# BatteryBoardV2.net
KiCad netlist of a schematic drawn in EAGLE
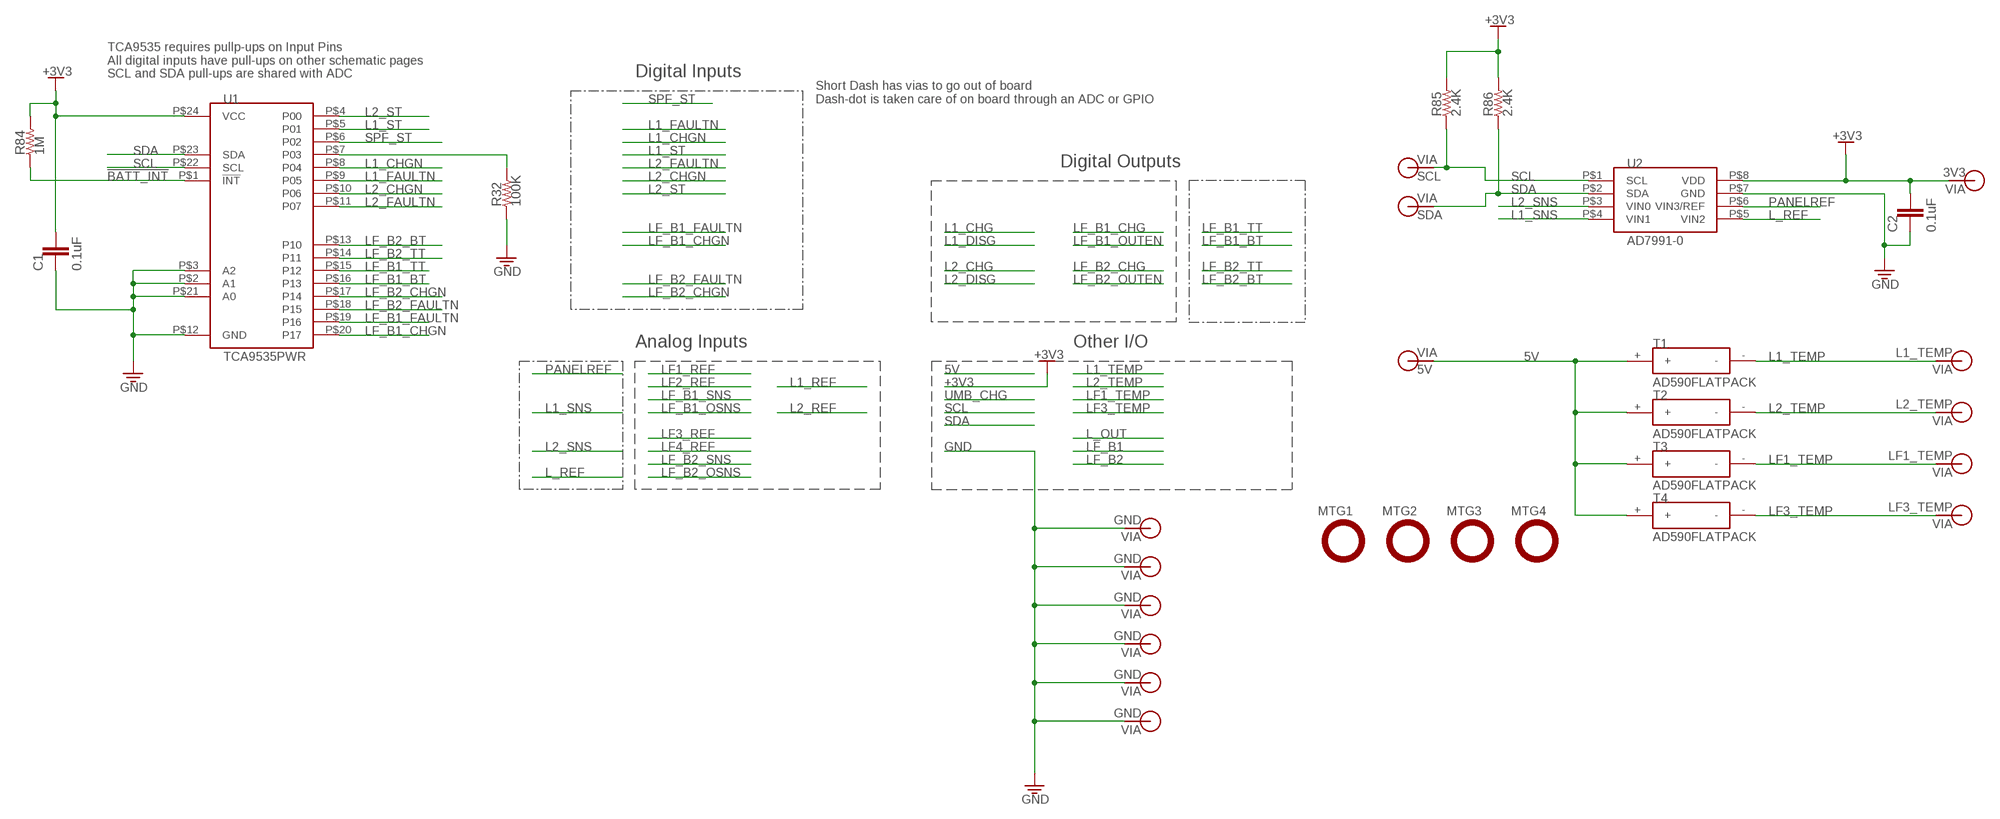
[diagram p0: schematic, sheet 1]
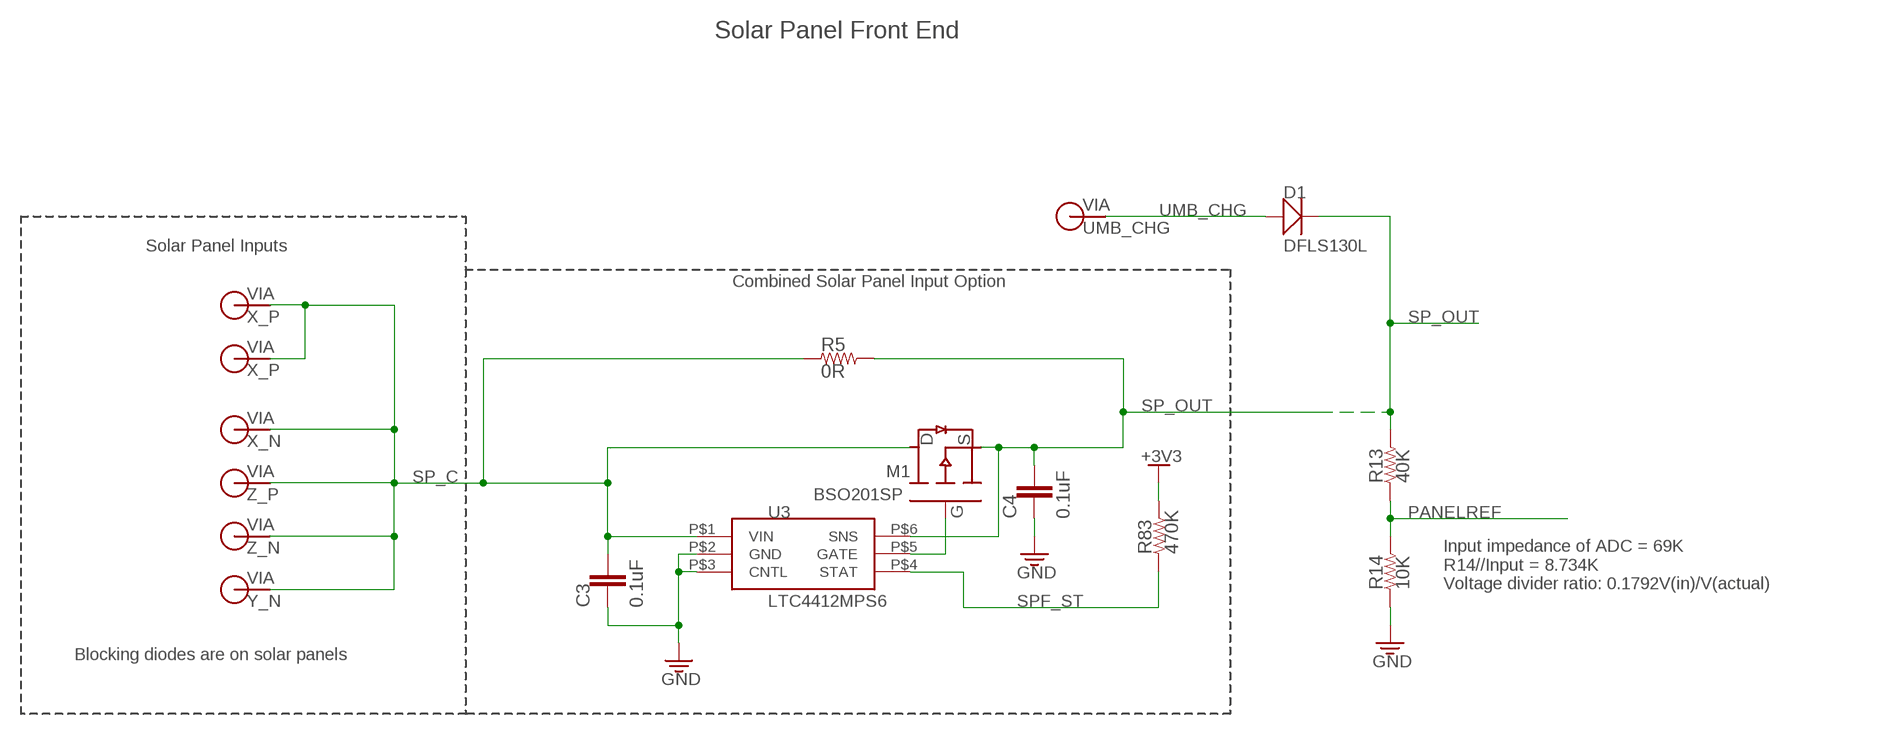
[diagram p1: schematic, sheet 2]
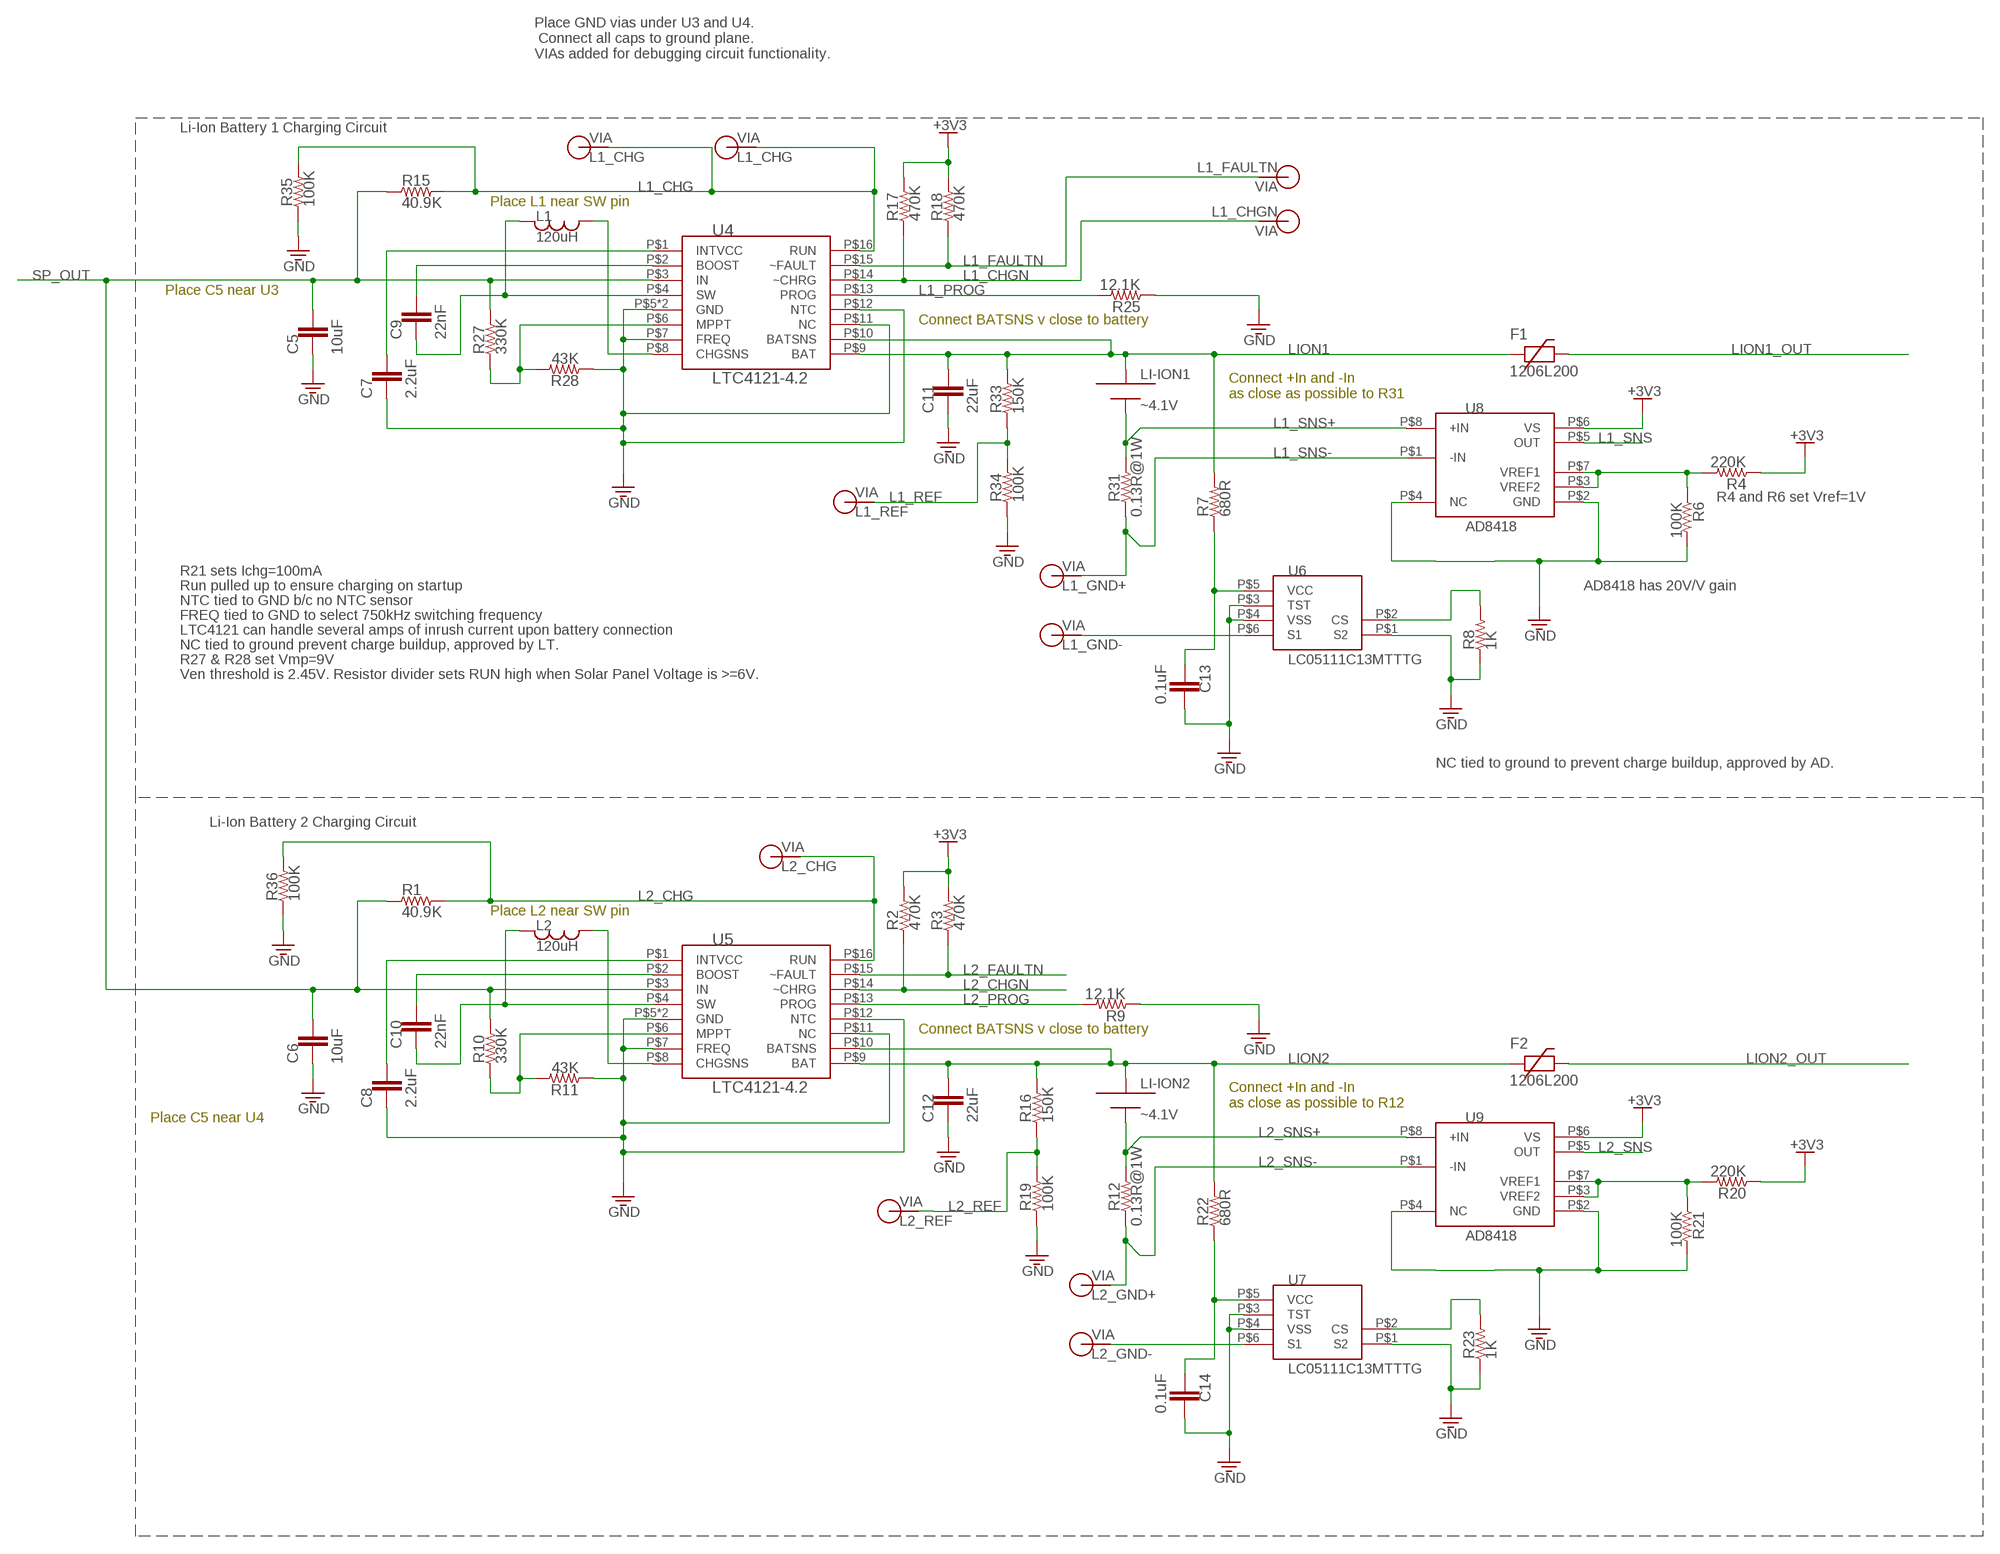
[diagram p2: schematic, sheet 3]
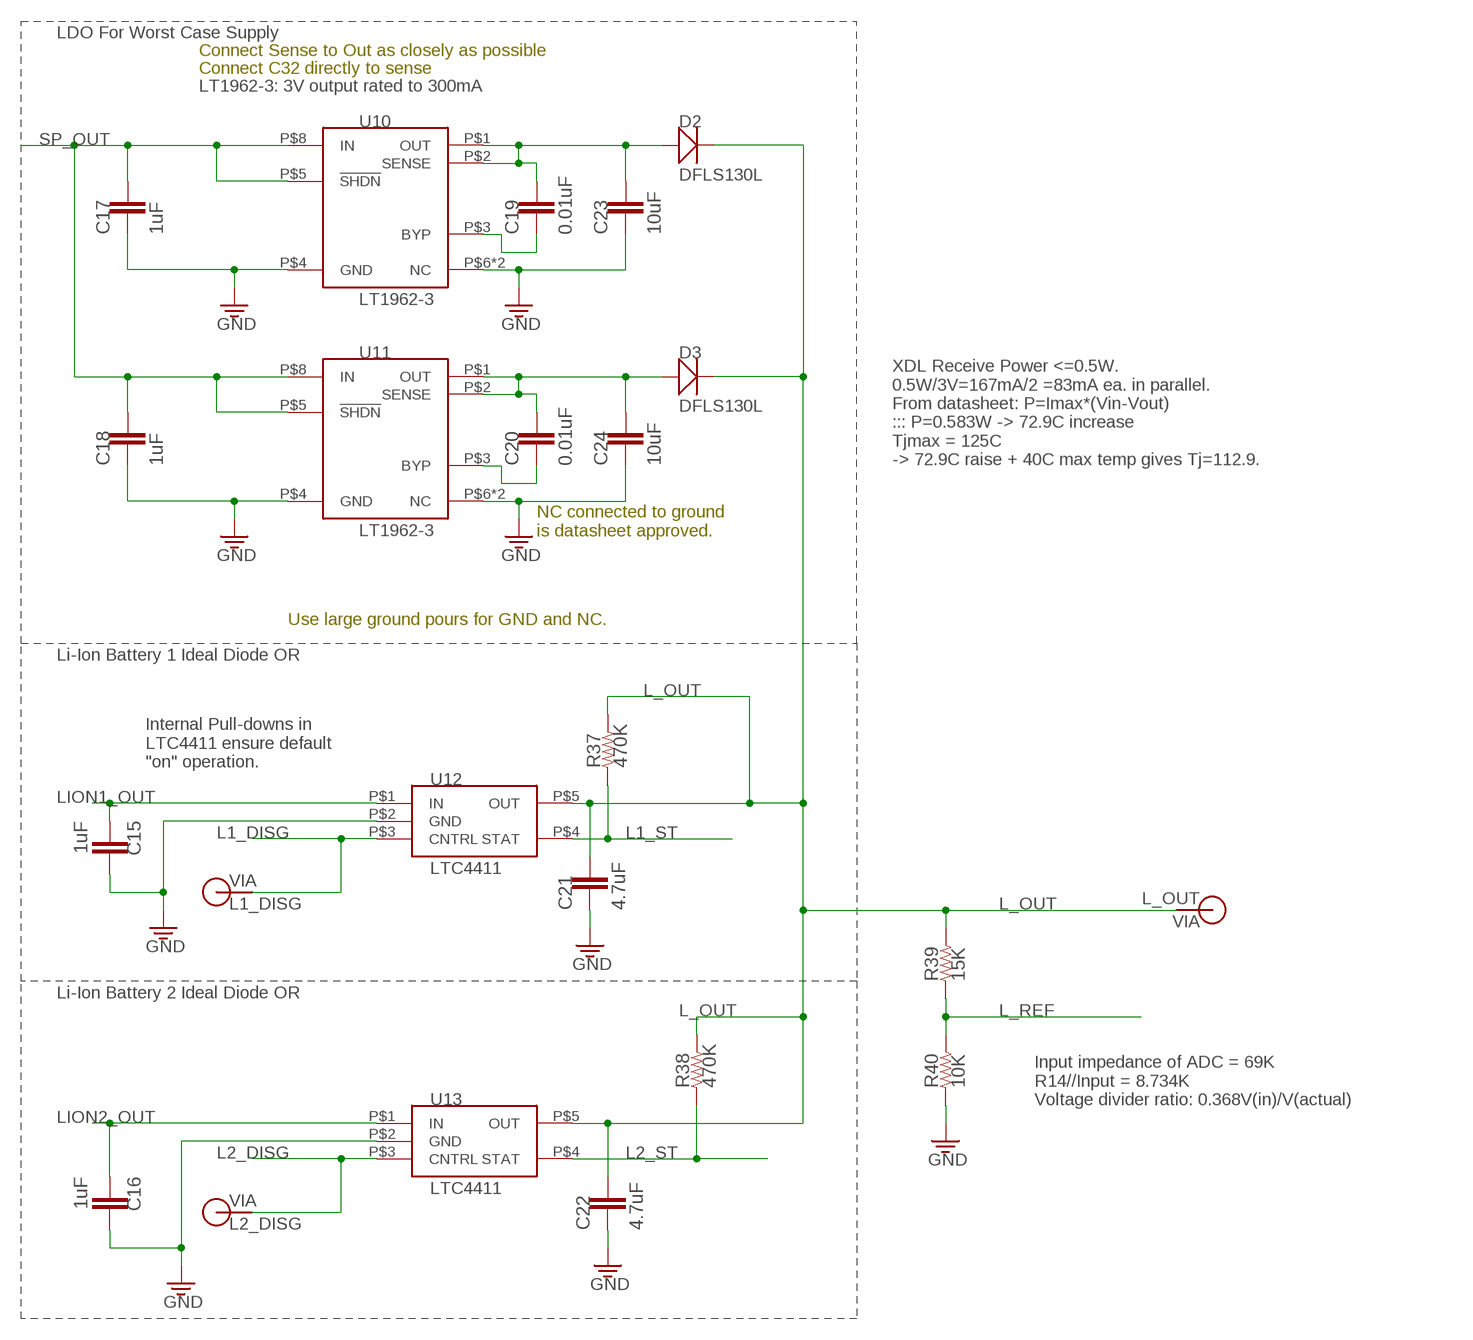
[diagram p3: schematic, sheet 4]
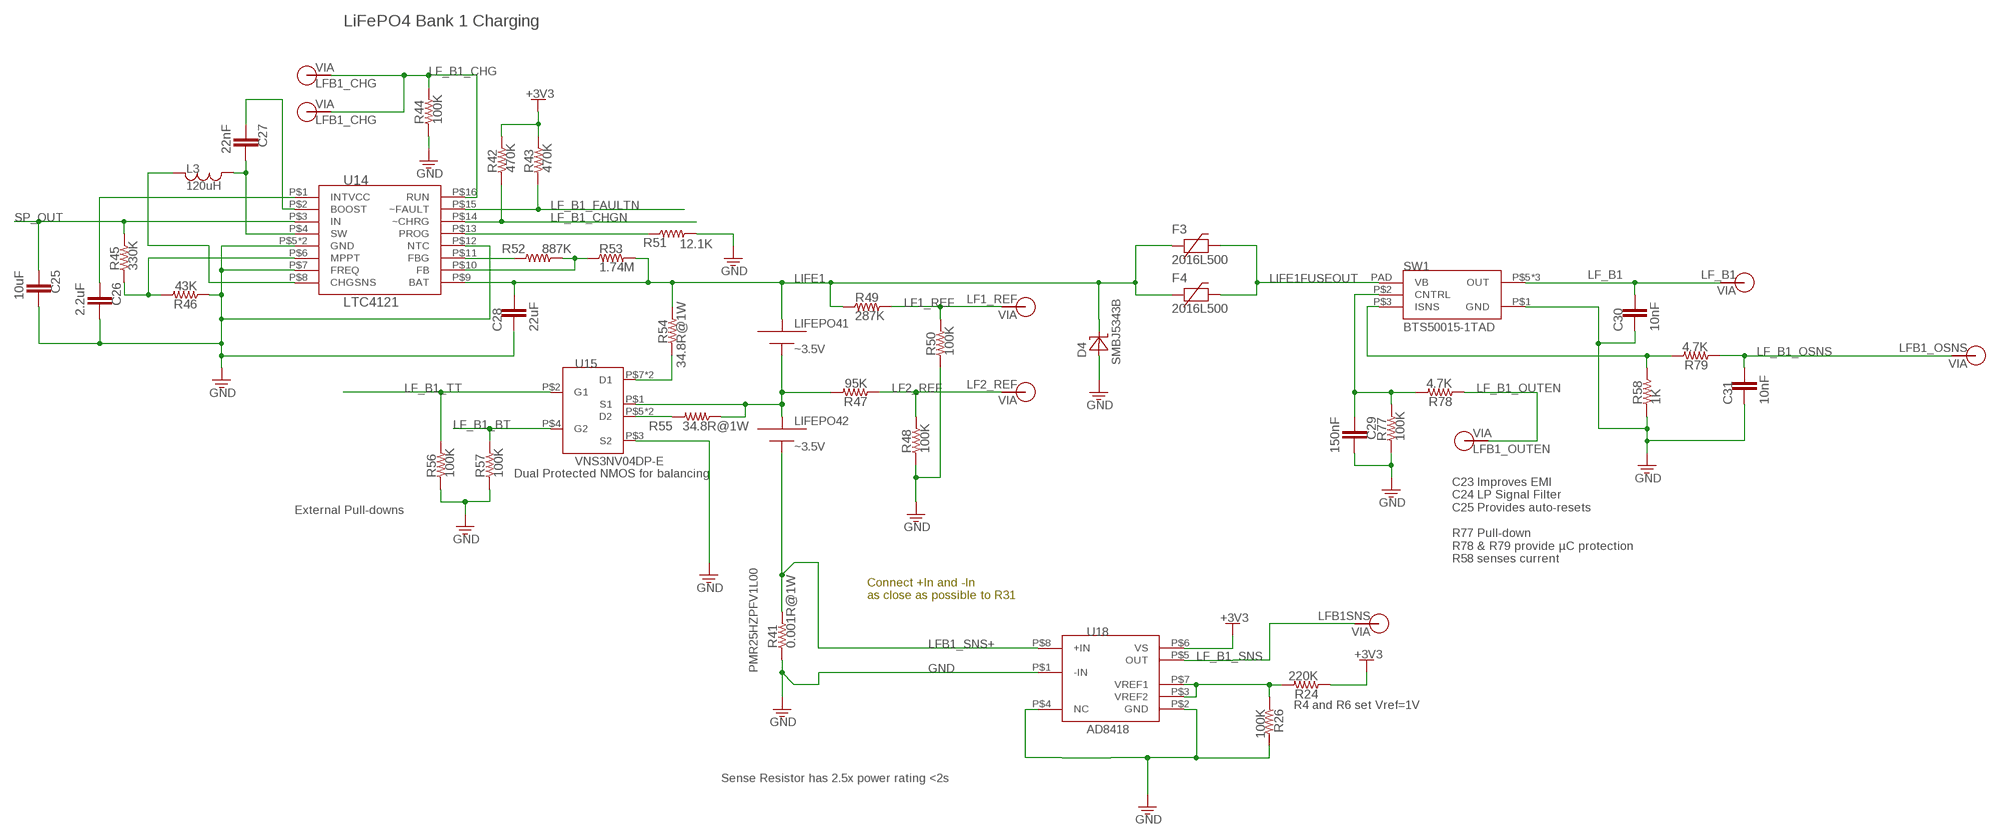
[diagram p4: schematic, sheet 5]
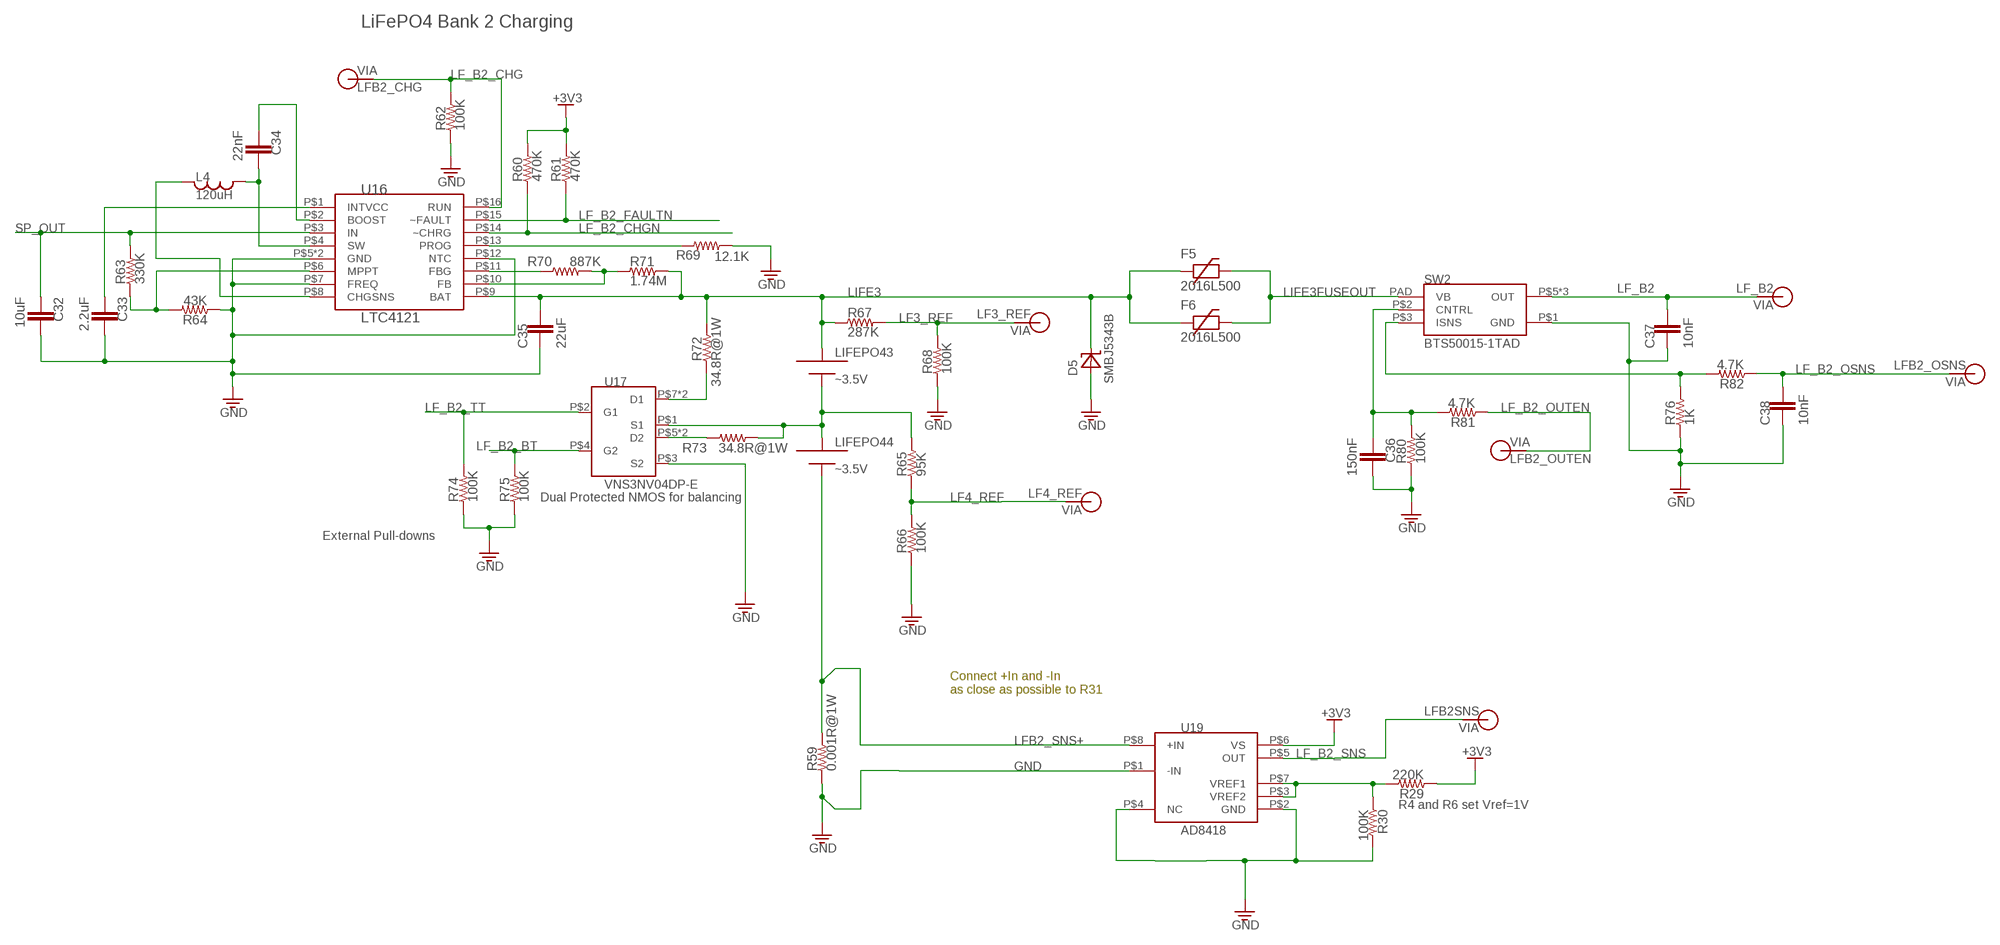
[diagram p5: schematic, sheet 6]

(export (version "E")
  (design (tool "Eeschema 10.0.6"))
  (components
    (comp (ref "C25")
      (value "10uF")
      (footprint "eagle-import:0805")
      (libsource (lib "eagle-import") (part "CAP0805"))
    )
    (comp (ref "C26")
      (value "2.2uF")
      (footprint "eagle-import:0805")
      (libsource (lib "eagle-import") (part "CAP0805"))
    )
    (comp (ref "C27")
      (value "22nF")
      (footprint "eagle-import:0805")
      (libsource (lib "eagle-import") (part "CAP0805"))
    )
    (comp (ref "C28")
      (value "22uF")
      (footprint "eagle-import:0805")
      (libsource (lib "eagle-import") (part "CAP0805"))
    )
    (comp (ref "C29")
      (value "150nF")
      (footprint "eagle-import:0805")
      (libsource (lib "eagle-import") (part "CAP0805"))
    )
    (comp (ref "C30")
      (value "10nF")
      (footprint "eagle-import:0805")
      (libsource (lib "eagle-import") (part "CAP0805"))
    )
    (comp (ref "C31")
      (value "10nF")
      (footprint "eagle-import:0805")
      (libsource (lib "eagle-import") (part "CAP0805"))
    )
    (comp (ref "D4")
      (value "SMBJ5343B")
      (footprint "eagle-import:DO214AA")
      (libsource (lib "eagle-import") (part "SMBJ5343B"))
    )
    (comp (ref "F3")
      (value "2016L500")
      (footprint "eagle-import:2016")
      (libsource (lib "eagle-import") (part "2016L500"))
    )
    (comp (ref "F4")
      (value "2016L500")
      (footprint "eagle-import:2016")
      (libsource (lib "eagle-import") (part "2016L500"))
    )
    (comp (ref "L3")
      (value "120uH")
      (footprint "eagle-import:1812")
      (libsource (lib "eagle-import") (part "IND1812"))
    )
    (comp (ref "LIFEPO41")
      (value "~3.5V")
      (footprint "eagle-import:EQUISAT-BATTERY-VA")
      (libsource (lib "eagle-import") (part "LIFEPO4VA"))
    )
    (comp (ref "LIFEPO42")
      (value "~3.5V")
      (footprint "eagle-import:EQUISAT-BATTERY-VB")
      (libsource (lib "eagle-import") (part "LIFEPO4VB"))
    )
    (comp (ref "R24")
      (value "220K")
      (footprint "eagle-import:0805")
      (libsource (lib "eagle-import") (part "RES0805"))
    )
    (comp (ref "R26")
      (value "100K")
      (footprint "eagle-import:0805")
      (libsource (lib "eagle-import") (part "RES0805"))
    )
    (comp (ref "R41")
      (value "0.001R@1W")
      (footprint "eagle-import:1210")
      (libsource (lib "eagle-import") (part "RES1210"))
    )
    (comp (ref "R42")
      (value "470K")
      (footprint "eagle-import:0805")
      (libsource (lib "eagle-import") (part "RES0805"))
    )
    (comp (ref "R43")
      (value "470K")
      (footprint "eagle-import:0805")
      (libsource (lib "eagle-import") (part "RES0805"))
    )
    (comp (ref "R44")
      (value "100K")
      (footprint "eagle-import:0805")
      (libsource (lib "eagle-import") (part "RES0805"))
    )
    (comp (ref "R45")
      (value "330K")
      (footprint "eagle-import:0805")
      (libsource (lib "eagle-import") (part "RES0805"))
    )
    (comp (ref "R46")
      (value "43K")
      (footprint "eagle-import:0805")
      (libsource (lib "eagle-import") (part "RES0805"))
    )
    (comp (ref "R47")
      (value "95K")
      (footprint "eagle-import:0805")
      (libsource (lib "eagle-import") (part "RES0805"))
    )
    (comp (ref "R48")
      (value "100K")
      (footprint "eagle-import:0805")
      (libsource (lib "eagle-import") (part "RES0805"))
    )
    (comp (ref "R49")
      (value "287K")
      (footprint "eagle-import:0805")
      (libsource (lib "eagle-import") (part "RES0805"))
    )
    (comp (ref "R50")
      (value "100K")
      (footprint "eagle-import:0805")
      (libsource (lib "eagle-import") (part "RES0805"))
    )
    (comp (ref "R51")
      (value "12.1K")
      (footprint "eagle-import:0805")
      (libsource (lib "eagle-import") (part "RES0805"))
    )
    (comp (ref "R52")
      (value "887K")
      (footprint "eagle-import:0805")
      (libsource (lib "eagle-import") (part "RES0805"))
    )
    (comp (ref "R53")
      (value "1.74M")
      (footprint "eagle-import:0805")
      (libsource (lib "eagle-import") (part "RES0805"))
    )
    (comp (ref "R54")
      (value "34.8R@1W")
      (footprint "eagle-import:1210")
      (libsource (lib "eagle-import") (part "RES1210"))
    )
    (comp (ref "R55")
      (value "34.8R@1W")
      (footprint "eagle-import:1210")
      (libsource (lib "eagle-import") (part "RES1210"))
    )
    (comp (ref "R56")
      (value "100K")
      (footprint "eagle-import:0805")
      (libsource (lib "eagle-import") (part "RES0805"))
    )
    (comp (ref "R57")
      (value "100K")
      (footprint "eagle-import:0805")
      (libsource (lib "eagle-import") (part "RES0805"))
    )
    (comp (ref "R58")
      (value "1K")
      (footprint "eagle-import:0805")
      (libsource (lib "eagle-import") (part "RES0805"))
    )
    (comp (ref "R77")
      (value "100K")
      (footprint "eagle-import:0805")
      (libsource (lib "eagle-import") (part "RES0805"))
    )
    (comp (ref "R78")
      (value "4.7K")
      (footprint "eagle-import:0805")
      (libsource (lib "eagle-import") (part "RES0805"))
    )
    (comp (ref "R79")
      (value "4.7K")
      (footprint "eagle-import:0805")
      (libsource (lib "eagle-import") (part "RES0805"))
    )
    (comp (ref "SW1")
      (value "BTS50015-1TAD")
      (footprint "eagle-import:TO-263-7-8")
      (libsource (lib "eagle-import") (part "BTS50015-1TAD"))
    )
    (comp (ref "U14")
      (value "LTC4121")
      (footprint "eagle-import:QFN-16-PAD")
      (libsource (lib "eagle-import") (part "LTC4121"))
    )
    (comp (ref "U15")
      (value "VNS3NV04DP-E")
      (footprint "eagle-import:SO-8")
      (libsource (lib "eagle-import") (part "VNS3NV04DP-E"))
    )
    (comp (ref "U18")
      (value "AD8418")
      (footprint "eagle-import:MSOP-8")
      (libsource (lib "eagle-import") (part "AD8418"))
    )
    (comp (ref "V32")
      (value "LFB1_CHG")
      (footprint "eagle-import:VIA-60MIL-SQ")
      (libsource (lib "eagle-import") (part "VIA60MIL-SQ"))
    )
    (comp (ref "V35")
      (value "LFB1_CHG")
      (footprint "eagle-import:VIA-60MIL")
      (libsource (lib "eagle-import") (part "VIA-60MIL"))
    )
    (comp (ref "V40")
      (value "LFB1SNS")
      (footprint "eagle-import:VIA-60MIL")
      (libsource (lib "eagle-import") (part "VIA-60MIL"))
    )
    (comp (ref "V41")
      (value "LF1_REF")
      (footprint "eagle-import:VIA-60MIL")
      (libsource (lib "eagle-import") (part "VIA-60MIL"))
    )
    (comp (ref "V42")
      (value "LF2_REF")
      (footprint "eagle-import:VIA-60MIL")
      (libsource (lib "eagle-import") (part "VIA-60MIL"))
    )
    (comp (ref "V43")
      (value "LFB1_OUTEN")
      (footprint "eagle-import:VIA-60MIL")
      (libsource (lib "eagle-import") (part "VIA-60MIL"))
    )
    (comp (ref "V45")
      (value "LF_B1")
      (footprint "eagle-import:VIA-120MIL")
      (libsource (lib "eagle-import") (part "VIA-120MIL"))
    )
    (comp (ref "V46")
      (value "LFB1_OSNS")
      (footprint "eagle-import:VIA-60MIL")
      (libsource (lib "eagle-import") (part "VIA-60MIL"))
    )
    (comp (ref "C15")
      (value "1uF")
      (footprint "eagle-import:0805")
      (libsource (lib "eagle-import") (part "CAP0805"))
    )
    (comp (ref "C16")
      (value "1uF")
      (footprint "eagle-import:0805")
      (libsource (lib "eagle-import") (part "CAP0805"))
    )
    (comp (ref "C17")
      (value "1uF")
      (footprint "eagle-import:0805")
      (libsource (lib "eagle-import") (part "CAP0805"))
    )
    (comp (ref "C18")
      (value "1uF")
      (footprint "eagle-import:0805")
      (libsource (lib "eagle-import") (part "CAP0805"))
    )
    (comp (ref "C19")
      (value "0.01uF")
      (footprint "eagle-import:0805")
      (libsource (lib "eagle-import") (part "CAP0805"))
    )
    (comp (ref "C20")
      (value "0.01uF")
      (footprint "eagle-import:0805")
      (libsource (lib "eagle-import") (part "CAP0805"))
    )
    (comp (ref "C21")
      (value "4.7uF")
      (footprint "eagle-import:0805")
      (libsource (lib "eagle-import") (part "CAP0805"))
    )
    (comp (ref "C22")
      (value "4.7uF")
      (footprint "eagle-import:0805")
      (libsource (lib "eagle-import") (part "CAP0805"))
    )
    (comp (ref "C23")
      (value "10uF")
      (footprint "eagle-import:0805")
      (libsource (lib "eagle-import") (part "CAP0805"))
    )
    (comp (ref "C24")
      (value "10uF")
      (footprint "eagle-import:0805")
      (libsource (lib "eagle-import") (part "CAP0805"))
    )
    (comp (ref "D2")
      (value "DFLS130L")
      (footprint "eagle-import:PWRDI-123")
      (libsource (lib "eagle-import") (part "DFLS130L"))
    )
    (comp (ref "D3")
      (value "DFLS130L")
      (footprint "eagle-import:PWRDI-123")
      (libsource (lib "eagle-import") (part "DFLS130L"))
    )
    (comp (ref "R37")
      (value "470K")
      (footprint "eagle-import:0805")
      (libsource (lib "eagle-import") (part "RES0805"))
    )
    (comp (ref "R38")
      (value "470K")
      (footprint "eagle-import:0805")
      (libsource (lib "eagle-import") (part "RES0805"))
    )
    (comp (ref "R39")
      (value "15K")
      (footprint "eagle-import:0805")
      (libsource (lib "eagle-import") (part "RES0805"))
    )
    (comp (ref "R40")
      (value "10K")
      (footprint "eagle-import:0805")
      (libsource (lib "eagle-import") (part "RES0805"))
    )
    (comp (ref "U10")
      (value "LT1962-3")
      (footprint "eagle-import:MSOP-8")
      (libsource (lib "eagle-import") (part "LT1962-3"))
    )
    (comp (ref "U11")
      (value "LT1962-3")
      (footprint "eagle-import:MSOP-8")
      (libsource (lib "eagle-import") (part "LT1962-3"))
    )
    (comp (ref "U12")
      (value "LTC4411")
      (footprint "eagle-import:TSOT23-5")
      (libsource (lib "eagle-import") (part "LTC4411"))
    )
    (comp (ref "U13")
      (value "LTC4411")
      (footprint "eagle-import:TSOT23-5")
      (libsource (lib "eagle-import") (part "LTC4411"))
    )
    (comp (ref "V29")
      (value "L1_DISG")
      (footprint "eagle-import:VIA-60MIL")
      (libsource (lib "eagle-import") (part "VIA-60MIL"))
    )
    (comp (ref "V30")
      (value "L2_DISG")
      (footprint "eagle-import:VIA-60MIL")
      (libsource (lib "eagle-import") (part "VIA-60MIL"))
    )
    (comp (ref "V34")
      (value "L_OUT")
      (footprint "eagle-import:VIA-120MIL")
      (libsource (lib "eagle-import") (part "VIA-120MIL"))
    )
    (comp (ref "C32")
      (value "10uF")
      (footprint "eagle-import:0805")
      (libsource (lib "eagle-import") (part "CAP0805"))
    )
    (comp (ref "C33")
      (value "2.2uF")
      (footprint "eagle-import:0805")
      (libsource (lib "eagle-import") (part "CAP0805"))
    )
    (comp (ref "C34")
      (value "22nF")
      (footprint "eagle-import:0805")
      (libsource (lib "eagle-import") (part "CAP0805"))
    )
    (comp (ref "C35")
      (value "22uF")
      (footprint "eagle-import:0805")
      (libsource (lib "eagle-import") (part "CAP0805"))
    )
    (comp (ref "C36")
      (value "150nF")
      (footprint "eagle-import:0805")
      (libsource (lib "eagle-import") (part "CAP0805"))
    )
    (comp (ref "C37")
      (value "10nF")
      (footprint "eagle-import:0805")
      (libsource (lib "eagle-import") (part "CAP0805"))
    )
    (comp (ref "C38")
      (value "10nF")
      (footprint "eagle-import:0805")
      (libsource (lib "eagle-import") (part "CAP0805"))
    )
    (comp (ref "D5")
      (value "SMBJ5343B")
      (footprint "eagle-import:DO214AA")
      (libsource (lib "eagle-import") (part "SMBJ5343B"))
    )
    (comp (ref "F5")
      (value "2016L500")
      (footprint "eagle-import:2016")
      (libsource (lib "eagle-import") (part "2016L500"))
    )
    (comp (ref "F6")
      (value "2016L500")
      (footprint "eagle-import:2016")
      (libsource (lib "eagle-import") (part "2016L500"))
    )
    (comp (ref "L4")
      (value "120uH")
      (footprint "eagle-import:1812")
      (libsource (lib "eagle-import") (part "IND1812"))
    )
    (comp (ref "LIFEPO43")
      (value "~3.5V")
      (footprint "eagle-import:EQUISAT-BATTERY-VA")
      (libsource (lib "eagle-import") (part "LIFEPO4VA"))
    )
    (comp (ref "LIFEPO44")
      (value "~3.5V")
      (footprint "eagle-import:EQUISAT-BATTERY-VB")
      (libsource (lib "eagle-import") (part "LIFEPO4VB"))
    )
    (comp (ref "R29")
      (value "220K")
      (footprint "eagle-import:0805")
      (libsource (lib "eagle-import") (part "RES0805"))
    )
    (comp (ref "R30")
      (value "100K")
      (footprint "eagle-import:0805")
      (libsource (lib "eagle-import") (part "RES0805"))
    )
    (comp (ref "R59")
      (value "0.001R@1W")
      (footprint "eagle-import:1210")
      (libsource (lib "eagle-import") (part "RES1210"))
    )
    (comp (ref "R60")
      (value "470K")
      (footprint "eagle-import:0805")
      (libsource (lib "eagle-import") (part "RES0805"))
    )
    (comp (ref "R61")
      (value "470K")
      (footprint "eagle-import:0805")
      (libsource (lib "eagle-import") (part "RES0805"))
    )
    (comp (ref "R62")
      (value "100K")
      (footprint "eagle-import:0805")
      (libsource (lib "eagle-import") (part "RES0805"))
    )
    (comp (ref "R63")
      (value "330K")
      (footprint "eagle-import:0805")
      (libsource (lib "eagle-import") (part "RES0805"))
    )
    (comp (ref "R64")
      (value "43K")
      (footprint "eagle-import:0805")
      (libsource (lib "eagle-import") (part "RES0805"))
    )
    (comp (ref "R65")
      (value "95K")
      (footprint "eagle-import:0805")
      (libsource (lib "eagle-import") (part "RES0805"))
    )
    (comp (ref "R66")
      (value "100K")
      (footprint "eagle-import:0805")
      (libsource (lib "eagle-import") (part "RES0805"))
    )
    (comp (ref "R67")
      (value "287K")
      (footprint "eagle-import:0805")
      (libsource (lib "eagle-import") (part "RES0805"))
    )
    (comp (ref "R68")
      (value "100K")
      (footprint "eagle-import:0805")
      (libsource (lib "eagle-import") (part "RES0805"))
    )
    (comp (ref "R69")
      (value "12.1K")
      (footprint "eagle-import:0805")
      (libsource (lib "eagle-import") (part "RES0805"))
    )
    (comp (ref "R70")
      (value "887K")
      (footprint "eagle-import:0805")
      (libsource (lib "eagle-import") (part "RES0805"))
    )
    (comp (ref "R71")
      (value "1.74M")
      (footprint "eagle-import:0805")
      (libsource (lib "eagle-import") (part "RES0805"))
    )
    (comp (ref "R72")
      (value "34.8R@1W")
      (footprint "eagle-import:1210")
      (libsource (lib "eagle-import") (part "RES1210"))
    )
    (comp (ref "R73")
      (value "34.8R@1W")
      (footprint "eagle-import:1210")
      (libsource (lib "eagle-import") (part "RES1210"))
    )
    (comp (ref "R74")
      (value "100K")
      (footprint "eagle-import:0805")
      (libsource (lib "eagle-import") (part "RES0805"))
    )
    (comp (ref "R75")
      (value "100K")
      (footprint "eagle-import:0805")
      (libsource (lib "eagle-import") (part "RES0805"))
    )
    (comp (ref "R76")
      (value "1K")
      (footprint "eagle-import:0805")
      (libsource (lib "eagle-import") (part "RES0805"))
    )
    (comp (ref "R80")
      (value "100K")
      (footprint "eagle-import:0805")
      (libsource (lib "eagle-import") (part "RES0805"))
    )
    (comp (ref "R81")
      (value "4.7K")
      (footprint "eagle-import:0805")
      (libsource (lib "eagle-import") (part "RES0805"))
    )
    (comp (ref "R82")
      (value "4.7K")
      (footprint "eagle-import:0805")
      (libsource (lib "eagle-import") (part "RES0805"))
    )
    (comp (ref "SW2")
      (value "BTS50015-1TAD")
      (footprint "eagle-import:TO-263-7-8")
      (libsource (lib "eagle-import") (part "BTS50015-1TAD"))
    )
    (comp (ref "U16")
      (value "LTC4121")
      (footprint "eagle-import:QFN-16-PAD")
      (libsource (lib "eagle-import") (part "LTC4121"))
    )
    (comp (ref "U17")
      (value "VNS3NV04DP-E")
      (footprint "eagle-import:SO-8")
      (libsource (lib "eagle-import") (part "VNS3NV04DP-E"))
    )
    (comp (ref "U19")
      (value "AD8418")
      (footprint "eagle-import:MSOP-8")
      (libsource (lib "eagle-import") (part "AD8418"))
    )
    (comp (ref "V44")
      (value "LFB2SNS")
      (footprint "eagle-import:VIA-60MIL")
      (libsource (lib "eagle-import") (part "VIA-60MIL"))
    )
    (comp (ref "V47")
      (value "LFB2_CHG")
      (footprint "eagle-import:VIA-60MIL")
      (libsource (lib "eagle-import") (part "VIA-60MIL"))
    )
    (comp (ref "V49")
      (value "LF3_REF")
      (footprint "eagle-import:VIA-60MIL")
      (libsource (lib "eagle-import") (part "VIA-60MIL"))
    )
    (comp (ref "V50")
      (value "LF4_REF")
      (footprint "eagle-import:VIA-60MIL")
      (libsource (lib "eagle-import") (part "VIA-60MIL"))
    )
    (comp (ref "V51")
      (value "LFB2_OUTEN")
      (footprint "eagle-import:VIA-60MIL")
      (libsource (lib "eagle-import") (part "VIA-60MIL"))
    )
    (comp (ref "V53")
      (value "LF_B2")
      (footprint "eagle-import:VIA-120MIL")
      (libsource (lib "eagle-import") (part "VIA-120MIL"))
    )
    (comp (ref "V99")
      (value "LFB2_OSNS")
      (footprint "eagle-import:VIA-60MIL")
      (libsource (lib "eagle-import") (part "VIA-60MIL"))
    )
    (comp (ref "C1")
      (value "0.1uF")
      (footprint "eagle-import:0805")
      (libsource (lib "eagle-import") (part "CAP0805"))
    )
    (comp (ref "C2")
      (value "0.1uF")
      (footprint "eagle-import:0805")
      (libsource (lib "eagle-import") (part "CAP0805"))
    )
    (comp (ref "MTG1")
      (value "MTG-NPTH-#2-CLOSE")
      (footprint "eagle-import:#2-CLOSE-NPTH")
      (libsource (lib "eagle-import") (part "MTG-NPTH-#2-CLOSE"))
    )
    (comp (ref "MTG2")
      (value "MTG-NPTH-#2-CLOSE")
      (footprint "eagle-import:#2-CLOSE-NPTH")
      (libsource (lib "eagle-import") (part "MTG-NPTH-#2-CLOSE"))
    )
    (comp (ref "MTG3")
      (value "MTG-NPTH-#2-CLOSE")
      (footprint "eagle-import:#2-CLOSE-NPTH")
      (libsource (lib "eagle-import") (part "MTG-NPTH-#2-CLOSE"))
    )
    (comp (ref "MTG4")
      (value "MTG-NPTH-#2-CLOSE")
      (footprint "eagle-import:#2-CLOSE-NPTH")
      (libsource (lib "eagle-import") (part "MTG-NPTH-#2-CLOSE"))
    )
    (comp (ref "R32")
      (value "100K")
      (footprint "eagle-import:0805")
      (libsource (lib "eagle-import") (part "RES0805"))
    )
    (comp (ref "R84")
      (value "1M")
      (footprint "eagle-import:0805")
      (libsource (lib "eagle-import") (part "RES0805"))
    )
    (comp (ref "R85")
      (value "2.4K")
      (footprint "eagle-import:0805")
      (libsource (lib "eagle-import") (part "RES0805"))
    )
    (comp (ref "R86")
      (value "2.4K")
      (footprint "eagle-import:0805")
      (libsource (lib "eagle-import") (part "RES0805"))
    )
    (comp (ref "T1")
      (value "AD590FLATPACK")
      (footprint "eagle-import:FLATPACK")
      (libsource (lib "eagle-import") (part "AD590FLATPACK"))
    )
    (comp (ref "T2")
      (value "AD590FLATPACK")
      (footprint "eagle-import:FLATPACK")
      (libsource (lib "eagle-import") (part "AD590FLATPACK"))
    )
    (comp (ref "T3")
      (value "AD590FLATPACK")
      (footprint "eagle-import:FLATPACK")
      (libsource (lib "eagle-import") (part "AD590FLATPACK"))
    )
    (comp (ref "T4")
      (value "AD590FLATPACK")
      (footprint "eagle-import:FLATPACK")
      (libsource (lib "eagle-import") (part "AD590FLATPACK"))
    )
    (comp (ref "U1")
      (value "TCA9535PWR")
      (footprint "eagle-import:TSSOP-24")
      (libsource (lib "eagle-import") (part "TCA9535PWR"))
    )
    (comp (ref "U2")
      (value "AD7991-0")
      (footprint "eagle-import:SOT-23-8")
      (libsource (lib "eagle-import") (part "AD7991-0"))
    )
    (comp (ref "V1")
      (value "GND")
      (footprint "eagle-import:VIA-120MIL")
      (libsource (lib "eagle-import") (part "VIA-120MIL"))
    )
    (comp (ref "V2")
      (value "GND")
      (footprint "eagle-import:VIA-120MIL")
      (libsource (lib "eagle-import") (part "VIA-120MIL"))
    )
    (comp (ref "V3")
      (value "GND")
      (footprint "eagle-import:VIA-60MIL-SQ")
      (libsource (lib "eagle-import") (part "VIA60MIL-SQ"))
    )
    (comp (ref "V4")
      (value "GND")
      (footprint "eagle-import:VIA-120MIL")
      (libsource (lib "eagle-import") (part "VIA-120MIL"))
    )
    (comp (ref "V5")
      (value "SCL")
      (footprint "eagle-import:VIA-60MIL")
      (libsource (lib "eagle-import") (part "VIA-60MIL"))
    )
    (comp (ref "V6")
      (value "SDA")
      (footprint "eagle-import:VIA-60MIL")
      (libsource (lib "eagle-import") (part "VIA-60MIL"))
    )
    (comp (ref "V7")
      (value "5V")
      (footprint "eagle-import:VIA-60MIL")
      (libsource (lib "eagle-import") (part "VIA-60MIL"))
    )
    (comp (ref "V8")
      (value "L1_TEMP")
      (footprint "eagle-import:VIA-60MIL")
      (libsource (lib "eagle-import") (part "VIA-60MIL"))
    )
    (comp (ref "V9")
      (value "L2_TEMP")
      (footprint "eagle-import:VIA-60MIL")
      (libsource (lib "eagle-import") (part "VIA-60MIL"))
    )
    (comp (ref "V10")
      (value "LF1_TEMP")
      (footprint "eagle-import:VIA-60MIL")
      (libsource (lib "eagle-import") (part "VIA-60MIL"))
    )
    (comp (ref "V11")
      (value "LF3_TEMP")
      (footprint "eagle-import:VIA-60MIL")
      (libsource (lib "eagle-import") (part "VIA-60MIL"))
    )
    (comp (ref "V12")
      (value "3V3")
      (footprint "eagle-import:VIA-60MIL")
      (libsource (lib "eagle-import") (part "VIA-60MIL"))
    )
    (comp (ref "V28")
      (value "GND")
      (footprint "eagle-import:VIA-60MIL-SQ")
      (libsource (lib "eagle-import") (part "VIA60MIL-SQ"))
    )
    (comp (ref "V36")
      (value "GND")
      (footprint "eagle-import:VIA-60MIL-SQ")
      (libsource (lib "eagle-import") (part "VIA60MIL-SQ"))
    )
    (comp (ref "C5")
      (value "10uF")
      (footprint "eagle-import:0805")
      (libsource (lib "eagle-import") (part "CAP0805"))
    )
    (comp (ref "C6")
      (value "10uF")
      (footprint "eagle-import:0805")
      (libsource (lib "eagle-import") (part "CAP0805"))
    )
    (comp (ref "C7")
      (value "2.2uF")
      (footprint "eagle-import:0805")
      (libsource (lib "eagle-import") (part "CAP0805"))
    )
    (comp (ref "C8")
      (value "2.2uF")
      (footprint "eagle-import:0805")
      (libsource (lib "eagle-import") (part "CAP0805"))
    )
    (comp (ref "C9")
      (value "22nF")
      (footprint "eagle-import:0805")
      (libsource (lib "eagle-import") (part "CAP0805"))
    )
    (comp (ref "C10")
      (value "22nF")
      (footprint "eagle-import:0805")
      (libsource (lib "eagle-import") (part "CAP0805"))
    )
    (comp (ref "C11")
      (value "22uF")
      (footprint "eagle-import:0805")
      (libsource (lib "eagle-import") (part "CAP0805"))
    )
    (comp (ref "C12")
      (value "22uF")
      (footprint "eagle-import:0805")
      (libsource (lib "eagle-import") (part "CAP0805"))
    )
    (comp (ref "C13")
      (value "0.1uF")
      (footprint "eagle-import:0805")
      (libsource (lib "eagle-import") (part "CAP0805"))
    )
    (comp (ref "C14")
      (value "0.1uF")
      (footprint "eagle-import:0805")
      (libsource (lib "eagle-import") (part "CAP0805"))
    )
    (comp (ref "F1")
      (value "1206L200")
      (footprint "eagle-import:1206")
      (libsource (lib "eagle-import") (part "PTCFUSE1206"))
    )
    (comp (ref "F2")
      (value "1206L200")
      (footprint "eagle-import:1206")
      (libsource (lib "eagle-import") (part "PTCFUSE1206"))
    )
    (comp (ref "L1")
      (value "120uH")
      (footprint "eagle-import:1812")
      (libsource (lib "eagle-import") (part "IND1812"))
    )
    (comp (ref "L2")
      (value "120uH")
      (footprint "eagle-import:1812")
      (libsource (lib "eagle-import") (part "IND1812"))
    )
    (comp (ref "LI-ION1")
      (value "~4.1V")
      (footprint "eagle-import:EQUISAT-BATTERY-VA")
      (libsource (lib "eagle-import") (part "LI-ION"))
    )
    (comp (ref "LI-ION2")
      (value "~4.1V")
      (footprint "eagle-import:EQUISAT-BATTERY-VA")
      (libsource (lib "eagle-import") (part "LI-ION"))
    )
    (comp (ref "R1")
      (value "40.9K")
      (footprint "eagle-import:0805")
      (libsource (lib "eagle-import") (part "RES0805"))
    )
    (comp (ref "R2")
      (value "470K")
      (footprint "eagle-import:0805")
      (libsource (lib "eagle-import") (part "RES0805"))
    )
    (comp (ref "R3")
      (value "470K")
      (footprint "eagle-import:0805")
      (libsource (lib "eagle-import") (part "RES0805"))
    )
    (comp (ref "R4")
      (value "220K")
      (footprint "eagle-import:0805")
      (libsource (lib "eagle-import") (part "RES0805"))
    )
    (comp (ref "R6")
      (value "100K")
      (footprint "eagle-import:0805")
      (libsource (lib "eagle-import") (part "RES0805"))
    )
    (comp (ref "R7")
      (value "680R")
      (footprint "eagle-import:0805")
      (libsource (lib "eagle-import") (part "RES0805"))
    )
    (comp (ref "R8")
      (value "1K")
      (footprint "eagle-import:0805")
      (libsource (lib "eagle-import") (part "RES0805"))
    )
    (comp (ref "R9")
      (value "12.1K")
      (footprint "eagle-import:0805")
      (libsource (lib "eagle-import") (part "RES0805"))
    )
    (comp (ref "R10")
      (value "330K")
      (footprint "eagle-import:0805")
      (libsource (lib "eagle-import") (part "RES0805"))
    )
    (comp (ref "R11")
      (value "43K")
      (footprint "eagle-import:0805")
      (libsource (lib "eagle-import") (part "RES0805"))
    )
    (comp (ref "R12")
      (value "0.13R@1W")
      (footprint "eagle-import:1210")
      (libsource (lib "eagle-import") (part "RES1210"))
    )
    (comp (ref "R15")
      (value "40.9K")
      (footprint "eagle-import:0805")
      (libsource (lib "eagle-import") (part "RES0805"))
    )
    (comp (ref "R16")
      (value "150K")
      (footprint "eagle-import:0805")
      (libsource (lib "eagle-import") (part "RES0805"))
    )
    (comp (ref "R17")
      (value "470K")
      (footprint "eagle-import:0805")
      (libsource (lib "eagle-import") (part "RES0805"))
    )
    (comp (ref "R18")
      (value "470K")
      (footprint "eagle-import:0805")
      (libsource (lib "eagle-import") (part "RES0805"))
    )
    (comp (ref "R19")
      (value "100K")
      (footprint "eagle-import:0805")
      (libsource (lib "eagle-import") (part "RES0805"))
    )
    (comp (ref "R20")
      (value "220K")
      (footprint "eagle-import:0805")
      (libsource (lib "eagle-import") (part "RES0805"))
    )
    (comp (ref "R21")
      (value "100K")
      (footprint "eagle-import:0805")
      (libsource (lib "eagle-import") (part "RES0805"))
    )
    (comp (ref "R22")
      (value "680R")
      (footprint "eagle-import:0805")
      (libsource (lib "eagle-import") (part "RES0805"))
    )
    (comp (ref "R23")
      (value "1K")
      (footprint "eagle-import:0805")
      (libsource (lib "eagle-import") (part "RES0805"))
    )
    (comp (ref "R25")
      (value "12.1K")
      (footprint "eagle-import:0805")
      (libsource (lib "eagle-import") (part "RES0805"))
    )
    (comp (ref "R27")
      (value "330K")
      (footprint "eagle-import:0805")
      (libsource (lib "eagle-import") (part "RES0805"))
    )
    (comp (ref "R28")
      (value "43K")
      (footprint "eagle-import:0805")
      (libsource (lib "eagle-import") (part "RES0805"))
    )
    (comp (ref "R31")
      (value "0.13R@1W")
      (footprint "eagle-import:1210")
      (libsource (lib "eagle-import") (part "RES1210"))
    )
    (comp (ref "R33")
      (value "150K")
      (footprint "eagle-import:0805")
      (libsource (lib "eagle-import") (part "RES0805"))
    )
    (comp (ref "R34")
      (value "100K")
      (footprint "eagle-import:0805")
      (libsource (lib "eagle-import") (part "RES0805"))
    )
    (comp (ref "R35")
      (value "100K")
      (footprint "eagle-import:0805")
      (libsource (lib "eagle-import") (part "RES0805"))
    )
    (comp (ref "R36")
      (value "100K")
      (footprint "eagle-import:0805")
      (libsource (lib "eagle-import") (part "RES0805"))
    )
    (comp (ref "U4")
      (value "LTC4121-4.2")
      (footprint "eagle-import:QFN-16-PAD")
      (libsource (lib "eagle-import") (part "LTC4121-4.2"))
    )
    (comp (ref "U5")
      (value "LTC4121-4.2")
      (footprint "eagle-import:QFN-16-PAD")
      (libsource (lib "eagle-import") (part "LTC4121-4.2"))
    )
    (comp (ref "U6")
      (value "LC05111C13MTTTG")
      (footprint "eagle-import:WDFN6")
      (libsource (lib "eagle-import") (part "LC05111C13MTTTG"))
    )
    (comp (ref "U7")
      (value "LC05111C13MTTTG")
      (footprint "eagle-import:WDFN6")
      (libsource (lib "eagle-import") (part "LC05111C13MTTTG"))
    )
    (comp (ref "U8")
      (value "AD8418")
      (footprint "eagle-import:MSOP-8")
      (libsource (lib "eagle-import") (part "AD8418"))
    )
    (comp (ref "U9")
      (value "AD8418")
      (footprint "eagle-import:MSOP-8")
      (libsource (lib "eagle-import") (part "AD8418"))
    )
    (comp (ref "V20")
      (value "L1_CHG")
      (footprint "eagle-import:VIA-60MIL")
      (libsource (lib "eagle-import") (part "VIA-60MIL"))
    )
    (comp (ref "V21")
      (value "L1_REF")
      (footprint "eagle-import:VIA-60MIL")
      (libsource (lib "eagle-import") (part "VIA-60MIL"))
    )
    (comp (ref "V22")
      (value "L1_GND+")
      (footprint "eagle-import:VIA-60MIL")
      (libsource (lib "eagle-import") (part "VIA-60MIL"))
    )
    (comp (ref "V23")
      (value "L1_GND-")
      (footprint "eagle-import:VIA-60MIL")
      (libsource (lib "eagle-import") (part "VIA-60MIL"))
    )
    (comp (ref "V24")
      (value "L2_GND+")
      (footprint "eagle-import:VIA-60MIL")
      (libsource (lib "eagle-import") (part "VIA-60MIL"))
    )
    (comp (ref "V25")
      (value "L2_GND-")
      (footprint "eagle-import:VIA-60MIL")
      (libsource (lib "eagle-import") (part "VIA-60MIL"))
    )
    (comp (ref "V26")
      (value "L1_FAULTN")
      (footprint "eagle-import:VIA-60MIL-SQ")
      (libsource (lib "eagle-import") (part "VIA60MIL-SQ"))
    )
    (comp (ref "V27")
      (value "L1_CHGN")
      (footprint "eagle-import:VIA-60MIL-SQ")
      (libsource (lib "eagle-import") (part "VIA60MIL-SQ"))
    )
    (comp (ref "V31")
      (value "L2_REF")
      (footprint "eagle-import:VIA-60MIL")
      (libsource (lib "eagle-import") (part "VIA-60MIL"))
    )
    (comp (ref "V33")
      (value "L2_CHG")
      (footprint "eagle-import:VIA-60MIL")
      (libsource (lib "eagle-import") (part "VIA-60MIL"))
    )
    (comp (ref "V48")
      (value "L1_CHG")
      (footprint "eagle-import:VIA-60MIL-SQ")
      (libsource (lib "eagle-import") (part "VIA60MIL-SQ"))
    )
    (comp (ref "C3")
      (value "0.1uF")
      (footprint "eagle-import:0805")
      (libsource (lib "eagle-import") (part "CAP0805"))
    )
    (comp (ref "C4")
      (value "0.1uF")
      (footprint "eagle-import:0805")
      (libsource (lib "eagle-import") (part "CAP0805"))
    )
    (comp (ref "D1")
      (value "DFLS130L")
      (footprint "eagle-import:PWRDI-123")
      (libsource (lib "eagle-import") (part "DFLS130L"))
    )
    (comp (ref "M1")
      (value "BSO201SP")
      (footprint "eagle-import:SO-8")
      (libsource (lib "eagle-import") (part "BSO201SP"))
    )
    (comp (ref "R5")
      (value "0R")
      (footprint "eagle-import:0805")
      (libsource (lib "eagle-import") (part "RES0805"))
    )
    (comp (ref "R13")
      (value "40K")
      (footprint "eagle-import:0805")
      (libsource (lib "eagle-import") (part "RES0805"))
    )
    (comp (ref "R14")
      (value "10K")
      (footprint "eagle-import:0805")
      (libsource (lib "eagle-import") (part "RES0805"))
    )
    (comp (ref "R83")
      (value "470K")
      (footprint "eagle-import:0805")
      (libsource (lib "eagle-import") (part "RES0805"))
    )
    (comp (ref "U3")
      (value "LTC4412MPS6")
      (footprint "eagle-import:TSOT23-6")
      (libsource (lib "eagle-import") (part "LTC4412"))
    )
    (comp (ref "V13")
      (value "X_P")
      (footprint "eagle-import:VIA-60MIL")
      (libsource (lib "eagle-import") (part "VIA-60MIL"))
    )
    (comp (ref "V14")
      (value "X_P")
      (footprint "eagle-import:VIA-60MIL-SQ")
      (libsource (lib "eagle-import") (part "VIA60MIL-SQ"))
    )
    (comp (ref "V15")
      (value "X_N")
      (footprint "eagle-import:VIA-60MIL")
      (libsource (lib "eagle-import") (part "VIA-60MIL"))
    )
    (comp (ref "V16")
      (value "Z_P")
      (footprint "eagle-import:VIA-60MIL")
      (libsource (lib "eagle-import") (part "VIA-60MIL"))
    )
    (comp (ref "V17")
      (value "Z_N")
      (footprint "eagle-import:VIA-60MIL")
      (libsource (lib "eagle-import") (part "VIA-60MIL"))
    )
    (comp (ref "V18")
      (value "Y_N")
      (footprint "eagle-import:VIA-60MIL")
      (libsource (lib "eagle-import") (part "VIA-60MIL"))
    )
    (comp (ref "V19")
      (value "UMB_CHG")
      (footprint "eagle-import:VIA-60MIL")
      (libsource (lib "eagle-import") (part "VIA-60MIL"))
    )
  )
  (nets
    (net (code "1") (name "+3V3") (class "Default")
      (node (ref "C1") (pin "1") (pinfunction "P$1_1") (pintype "passive"))
      (node (ref "C2") (pin "1") (pinfunction "P$1_1") (pintype "passive"))
      (node (ref "R17") (pin "2") (pinfunction "2_2") (pintype "passive"))
      (node (ref "R18") (pin "2") (pinfunction "2_2") (pintype "passive"))
      (node (ref "R2") (pin "2") (pinfunction "2_2") (pintype "passive"))
      (node (ref "R20") (pin "1") (pinfunction "1_1") (pintype "passive"))
      (node (ref "R24") (pin "1") (pinfunction "1_1") (pintype "passive"))
      (node (ref "R29") (pin "1") (pinfunction "1_1") (pintype "passive"))
      (node (ref "R3") (pin "2") (pinfunction "2_2") (pintype "passive"))
      (node (ref "R4") (pin "1") (pinfunction "1_1") (pintype "passive"))
      (node (ref "R42") (pin "2") (pinfunction "2_2") (pintype "passive"))
      (node (ref "R43") (pin "2") (pinfunction "2_2") (pintype "passive"))
      (node (ref "R60") (pin "2") (pinfunction "2_2") (pintype "passive"))
      (node (ref "R61") (pin "2") (pinfunction "2_2") (pintype "passive"))
      (node (ref "R83") (pin "2") (pinfunction "2_2") (pintype "passive"))
      (node (ref "R84") (pin "2") (pinfunction "2_2") (pintype "passive"))
      (node (ref "R85") (pin "2") (pinfunction "2_2") (pintype "passive"))
      (node (ref "R86") (pin "2") (pinfunction "2_2") (pintype "passive"))
      (node (ref "U1") (pin "P$24") (pinfunction "VCC_P$24") (pintype "power_in"))
      (node (ref "U18") (pin "P$6") (pinfunction "VS_P$6") (pintype "bidirectional"))
      (node (ref "U19") (pin "P$6") (pinfunction "VS_P$6") (pintype "bidirectional"))
      (node (ref "U2") (pin "P$8") (pinfunction "VDD_P$8") (pintype "bidirectional"))
      (node (ref "U8") (pin "P$6") (pinfunction "VS_P$6") (pintype "bidirectional"))
      (node (ref "U9") (pin "P$6") (pinfunction "VS_P$6") (pintype "bidirectional"))
      (node (ref "V12") (pin "P$1") (pinfunction "P$1_P$1") (pintype "bidirectional"))
    )
    (net (code "2") (name "5V") (class "Default")
      (node (ref "T1") (pin "+") (pinfunction "+_+") (pintype "bidirectional"))
      (node (ref "T2") (pin "+") (pinfunction "+_+") (pintype "bidirectional"))
      (node (ref "T3") (pin "+") (pinfunction "+_+") (pintype "bidirectional"))
      (node (ref "T4") (pin "+") (pinfunction "+_+") (pintype "bidirectional"))
      (node (ref "V7") (pin "P$1") (pinfunction "P$1_P$1") (pintype "bidirectional"))
    )
    (net (code "3") (name "GND") (class "Default")
      (node (ref "C1") (pin "2") (pinfunction "P$2_2") (pintype "passive"))
      (node (ref "C11") (pin "2") (pinfunction "P$2_2") (pintype "passive"))
      (node (ref "C12") (pin "2") (pinfunction "P$2_2") (pintype "passive"))
      (node (ref "C13") (pin "1") (pinfunction "P$1_1") (pintype "passive"))
      (node (ref "C14") (pin "1") (pinfunction "P$1_1") (pintype "passive"))
      (node (ref "C15") (pin "1") (pinfunction "P$1_1") (pintype "passive"))
      (node (ref "C16") (pin "1") (pinfunction "P$1_1") (pintype "passive"))
      (node (ref "C17") (pin "2") (pinfunction "P$2_2") (pintype "passive"))
      (node (ref "C18") (pin "2") (pinfunction "P$2_2") (pintype "passive"))
      (node (ref "C2") (pin "2") (pinfunction "P$2_2") (pintype "passive"))
      (node (ref "C21") (pin "2") (pinfunction "P$2_2") (pintype "passive"))
      (node (ref "C22") (pin "2") (pinfunction "P$2_2") (pintype "passive"))
      (node (ref "C23") (pin "2") (pinfunction "P$2_2") (pintype "passive"))
      (node (ref "C24") (pin "2") (pinfunction "P$2_2") (pintype "passive"))
      (node (ref "C25") (pin "1") (pinfunction "P$1_1") (pintype "passive"))
      (node (ref "C26") (pin "1") (pinfunction "P$1_1") (pintype "passive"))
      (node (ref "C28") (pin "2") (pinfunction "P$2_2") (pintype "passive"))
      (node (ref "C29") (pin "1") (pinfunction "P$1_1") (pintype "passive"))
      (node (ref "C3") (pin "2") (pinfunction "P$2_2") (pintype "passive"))
      (node (ref "C30") (pin "2") (pinfunction "P$2_2") (pintype "passive"))
      (node (ref "C31") (pin "2") (pinfunction "P$2_2") (pintype "passive"))
      (node (ref "C32") (pin "1") (pinfunction "P$1_1") (pintype "passive"))
      (node (ref "C33") (pin "1") (pinfunction "P$1_1") (pintype "passive"))
      (node (ref "C35") (pin "2") (pinfunction "P$2_2") (pintype "passive"))
      (node (ref "C36") (pin "1") (pinfunction "P$1_1") (pintype "passive"))
      (node (ref "C37") (pin "2") (pinfunction "P$2_2") (pintype "passive"))
      (node (ref "C38") (pin "2") (pinfunction "P$2_2") (pintype "passive"))
      (node (ref "C4") (pin "2") (pinfunction "P$2_2") (pintype "passive"))
      (node (ref "C5") (pin "2") (pinfunction "P$2_2") (pintype "passive"))
      (node (ref "C6") (pin "2") (pinfunction "P$2_2") (pintype "passive"))
      (node (ref "C7") (pin "2") (pinfunction "P$2_2") (pintype "passive"))
      (node (ref "C8") (pin "2") (pinfunction "P$2_2") (pintype "passive"))
      (node (ref "D4") (pin "A") (pinfunction "A_A") (pintype "passive"))
      (node (ref "D5") (pin "A") (pinfunction "A_A") (pintype "passive"))
      (node (ref "R11") (pin "1") (pinfunction "1_1") (pintype "passive"))
      (node (ref "R14") (pin "1") (pinfunction "1_1") (pintype "passive"))
      (node (ref "R19") (pin "1") (pinfunction "1_1") (pintype "passive"))
      (node (ref "R21") (pin "2") (pinfunction "2_2") (pintype "passive"))
      (node (ref "R23") (pin "1") (pinfunction "1_1") (pintype "passive"))
      (node (ref "R25") (pin "1") (pinfunction "1_1") (pintype "passive"))
      (node (ref "R26") (pin "2") (pinfunction "2_2") (pintype "passive"))
      (node (ref "R28") (pin "1") (pinfunction "1_1") (pintype "passive"))
      (node (ref "R30") (pin "2") (pinfunction "2_2") (pintype "passive"))
      (node (ref "R32") (pin "1") (pinfunction "1_1") (pintype "passive"))
      (node (ref "R34") (pin "1") (pinfunction "1_1") (pintype "passive"))
      (node (ref "R35") (pin "1") (pinfunction "1_1") (pintype "passive"))
      (node (ref "R36") (pin "1") (pinfunction "1_1") (pintype "passive"))
      (node (ref "R40") (pin "1") (pinfunction "1_1") (pintype "passive"))
      (node (ref "R41") (pin "P$1") (pinfunction "1_P$1") (pintype "passive"))
      (node (ref "R44") (pin "1") (pinfunction "1_1") (pintype "passive"))
      (node (ref "R46") (pin "1") (pinfunction "1_1") (pintype "passive"))
      (node (ref "R48") (pin "1") (pinfunction "1_1") (pintype "passive"))
      (node (ref "R50") (pin "1") (pinfunction "1_1") (pintype "passive"))
      (node (ref "R51") (pin "2") (pinfunction "2_2") (pintype "passive"))
      (node (ref "R56") (pin "1") (pinfunction "1_1") (pintype "passive"))
      (node (ref "R57") (pin "1") (pinfunction "1_1") (pintype "passive"))
      (node (ref "R58") (pin "1") (pinfunction "1_1") (pintype "passive"))
      (node (ref "R59") (pin "P$1") (pinfunction "1_P$1") (pintype "passive"))
      (node (ref "R6") (pin "2") (pinfunction "2_2") (pintype "passive"))
      (node (ref "R62") (pin "1") (pinfunction "1_1") (pintype "passive"))
      (node (ref "R64") (pin "1") (pinfunction "1_1") (pintype "passive"))
      (node (ref "R66") (pin "1") (pinfunction "1_1") (pintype "passive"))
      (node (ref "R68") (pin "1") (pinfunction "1_1") (pintype "passive"))
      (node (ref "R69") (pin "2") (pinfunction "2_2") (pintype "passive"))
      (node (ref "R74") (pin "1") (pinfunction "1_1") (pintype "passive"))
      (node (ref "R75") (pin "1") (pinfunction "1_1") (pintype "passive"))
      (node (ref "R76") (pin "1") (pinfunction "1_1") (pintype "passive"))
      (node (ref "R77") (pin "1") (pinfunction "1_1") (pintype "passive"))
      (node (ref "R8") (pin "1") (pinfunction "1_1") (pintype "passive"))
      (node (ref "R80") (pin "1") (pinfunction "1_1") (pintype "passive"))
      (node (ref "R9") (pin "1") (pinfunction "1_1") (pintype "passive"))
      (node (ref "SW1") (pin "P$1") (pinfunction "GND_P$1") (pintype "bidirectional"))
      (node (ref "SW2") (pin "P$1") (pinfunction "GND_P$1") (pintype "bidirectional"))
      (node (ref "U1") (pin "P$12") (pinfunction "GND_P$12") (pintype "power_in"))
      (node (ref "U1") (pin "P$2") (pinfunction "A1_P$2") (pintype "bidirectional"))
      (node (ref "U1") (pin "P$21") (pinfunction "A0_P$21") (pintype "bidirectional"))
      (node (ref "U1") (pin "P$3") (pinfunction "A2_P$3") (pintype "bidirectional"))
      (node (ref "U10") (pin "P$4") (pinfunction "GND_P$4") (pintype "bidirectional"))
      (node (ref "U10") (pin "P$6") (pinfunction "NC_P$6") (pintype "bidirectional"))
      (node (ref "U10") (pin "P$7") (pinfunction "NC_P$7") (pintype "bidirectional"))
      (node (ref "U11") (pin "P$4") (pinfunction "GND_P$4") (pintype "bidirectional"))
      (node (ref "U11") (pin "P$6") (pinfunction "NC_P$6") (pintype "bidirectional"))
      (node (ref "U11") (pin "P$7") (pinfunction "NC_P$7") (pintype "bidirectional"))
      (node (ref "U12") (pin "P$2") (pinfunction "GND_P$2") (pintype "bidirectional"))
      (node (ref "U13") (pin "P$2") (pinfunction "GND_P$2") (pintype "bidirectional"))
      (node (ref "U14") (pin "P$12") (pinfunction "NTC_P$12") (pintype "bidirectional"))
      (node (ref "U14") (pin "P$17") (pinfunction "GND_P$17") (pintype "bidirectional"))
      (node (ref "U14") (pin "P$5") (pinfunction "GND_P$5") (pintype "bidirectional"))
      (node (ref "U14") (pin "P$7") (pinfunction "FREQ_P$7") (pintype "bidirectional"))
      (node (ref "U15") (pin "P$3") (pinfunction "S2_P$3") (pintype "bidirectional"))
      (node (ref "U16") (pin "P$12") (pinfunction "NTC_P$12") (pintype "bidirectional"))
      (node (ref "U16") (pin "P$17") (pinfunction "GND_P$17") (pintype "bidirectional"))
      (node (ref "U16") (pin "P$5") (pinfunction "GND_P$5") (pintype "bidirectional"))
      (node (ref "U16") (pin "P$7") (pinfunction "FREQ_P$7") (pintype "bidirectional"))
      (node (ref "U17") (pin "P$3") (pinfunction "S2_P$3") (pintype "bidirectional"))
      (node (ref "U18") (pin "P$1") (pinfunction "-IN_P$1") (pintype "bidirectional"))
      (node (ref "U18") (pin "P$2") (pinfunction "GND_P$2") (pintype "bidirectional"))
      (node (ref "U18") (pin "P$4") (pinfunction "NC_P$4") (pintype "bidirectional"))
      (node (ref "U19") (pin "P$1") (pinfunction "-IN_P$1") (pintype "bidirectional"))
      (node (ref "U19") (pin "P$2") (pinfunction "GND_P$2") (pintype "bidirectional"))
      (node (ref "U19") (pin "P$4") (pinfunction "NC_P$4") (pintype "bidirectional"))
      (node (ref "U2") (pin "P$7") (pinfunction "GND_P$7") (pintype "bidirectional"))
      (node (ref "U3") (pin "P$2") (pinfunction "GND_P$2") (pintype "bidirectional"))
      (node (ref "U3") (pin "P$3") (pinfunction "CNTL_P$3") (pintype "bidirectional"))
      (node (ref "U4") (pin "P$11") (pinfunction "NC_P$11") (pintype "bidirectional"))
      (node (ref "U4") (pin "P$12") (pinfunction "NTC_P$12") (pintype "bidirectional"))
      (node (ref "U4") (pin "P$17") (pinfunction "GND_P$17") (pintype "bidirectional"))
      (node (ref "U4") (pin "P$5") (pinfunction "GND_P$5") (pintype "bidirectional"))
      (node (ref "U4") (pin "P$7") (pinfunction "FREQ_P$7") (pintype "bidirectional"))
      (node (ref "U5") (pin "P$11") (pinfunction "NC_P$11") (pintype "bidirectional"))
      (node (ref "U5") (pin "P$12") (pinfunction "NTC_P$12") (pintype "bidirectional"))
      (node (ref "U5") (pin "P$17") (pinfunction "GND_P$17") (pintype "bidirectional"))
      (node (ref "U5") (pin "P$5") (pinfunction "GND_P$5") (pintype "bidirectional"))
      (node (ref "U5") (pin "P$7") (pinfunction "FREQ_P$7") (pintype "bidirectional"))
      (node (ref "U6") (pin "P$1") (pinfunction "S2_P$1") (pintype "bidirectional"))
      (node (ref "U6") (pin "P$3") (pinfunction "TST_P$3") (pintype "bidirectional"))
      (node (ref "U6") (pin "P$4") (pinfunction "VSS_P$4") (pintype "bidirectional"))
      (node (ref "U7") (pin "P$1") (pinfunction "S2_P$1") (pintype "bidirectional"))
      (node (ref "U7") (pin "P$3") (pinfunction "TST_P$3") (pintype "bidirectional"))
      (node (ref "U7") (pin "P$4") (pinfunction "VSS_P$4") (pintype "bidirectional"))
      (node (ref "U8") (pin "P$2") (pinfunction "GND_P$2") (pintype "bidirectional"))
      (node (ref "U8") (pin "P$4") (pinfunction "NC_P$4") (pintype "bidirectional"))
      (node (ref "U9") (pin "P$2") (pinfunction "GND_P$2") (pintype "bidirectional"))
      (node (ref "U9") (pin "P$4") (pinfunction "NC_P$4") (pintype "bidirectional"))
      (node (ref "V1") (pin "P$1") (pinfunction "P$1_P$1") (pintype "bidirectional"))
      (node (ref "V2") (pin "P$1") (pinfunction "P$1_P$1") (pintype "bidirectional"))
      (node (ref "V28") (pin "P$1") (pinfunction "P$1_P$1") (pintype "bidirectional"))
      (node (ref "V3") (pin "P$1") (pinfunction "P$1_P$1") (pintype "bidirectional"))
      (node (ref "V36") (pin "P$1") (pinfunction "P$1_P$1") (pintype "bidirectional"))
      (node (ref "V4") (pin "P$1") (pinfunction "P$1_P$1") (pintype "bidirectional"))
    )
    (net (code "4") (name "L1_CHG") (class "Default")
      (node (ref "R15") (pin "2") (pinfunction "2_2") (pintype "passive"))
      (node (ref "R35") (pin "2") (pinfunction "2_2") (pintype "passive"))
      (node (ref "U4") (pin "P$16") (pinfunction "RUN_P$16") (pintype "bidirectional"))
      (node (ref "V20") (pin "P$1") (pinfunction "P$1_P$1") (pintype "bidirectional"))
      (node (ref "V48") (pin "P$1") (pinfunction "P$1_P$1") (pintype "bidirectional"))
    )
    (net (code "5") (name "L1_CHGN") (class "Default")
      (node (ref "R17") (pin "1") (pinfunction "1_1") (pintype "passive"))
      (node (ref "U1") (pin "P$8") (pinfunction "P04_P$8") (pintype "bidirectional"))
      (node (ref "U4") (pin "P$14") (pinfunction "~{CHRG}_P$14") (pintype "bidirectional"))
      (node (ref "V27") (pin "P$1") (pinfunction "P$1_P$1") (pintype "bidirectional"))
    )
    (net (code "6") (name "L1_DISG") (class "Default")
      (node (ref "U12") (pin "P$3") (pinfunction "CNTRL_P$3") (pintype "bidirectional"))
      (node (ref "V29") (pin "P$1") (pinfunction "P$1_P$1") (pintype "bidirectional"))
    )
    (net (code "7") (name "L1_FAULTN") (class "Default")
      (node (ref "R18") (pin "1") (pinfunction "1_1") (pintype "passive"))
      (node (ref "U1") (pin "P$9") (pinfunction "P05_P$9") (pintype "bidirectional"))
      (node (ref "U4") (pin "P$15") (pinfunction "~{FAULT}_P$15") (pintype "bidirectional"))
      (node (ref "V26") (pin "P$1") (pinfunction "P$1_P$1") (pintype "bidirectional"))
    )
    (net (code "8") (name "L1_PROG") (class "Default")
      (node (ref "R25") (pin "2") (pinfunction "2_2") (pintype "passive"))
      (node (ref "U4") (pin "P$13") (pinfunction "PROG_P$13") (pintype "bidirectional"))
    )
    (net (code "9") (name "L1_REF") (class "Default")
      (node (ref "R33") (pin "1") (pinfunction "1_1") (pintype "passive"))
      (node (ref "R34") (pin "2") (pinfunction "2_2") (pintype "passive"))
      (node (ref "V21") (pin "P$1") (pinfunction "P$1_P$1") (pintype "bidirectional"))
    )
    (net (code "10") (name "L1_SNS") (class "Default")
      (node (ref "U2") (pin "P$4") (pinfunction "VIN1_P$4") (pintype "bidirectional"))
      (node (ref "U8") (pin "P$5") (pinfunction "OUT_P$5") (pintype "bidirectional"))
    )
    (net (code "11") (name "L1_SNS+") (class "Default")
      (node (ref "LI-ION1") (pin "MINUS") (pinfunction "MINUS_MINUS") (pintype "power_in"))
      (node (ref "R31") (pin "P$2") (pinfunction "2_P$2") (pintype "passive"))
      (node (ref "U8") (pin "P$8") (pinfunction "+IN_P$8") (pintype "bidirectional"))
    )
    (net (code "12") (name "L1_SNS-") (class "Default")
      (node (ref "R31") (pin "P$1") (pinfunction "1_P$1") (pintype "passive"))
      (node (ref "U8") (pin "P$1") (pinfunction "-IN_P$1") (pintype "bidirectional"))
      (node (ref "V22") (pin "P$1") (pinfunction "P$1_P$1") (pintype "bidirectional"))
    )
    (net (code "13") (name "L1_ST") (class "Default")
      (node (ref "R37") (pin "1") (pinfunction "1_1") (pintype "passive"))
      (node (ref "U1") (pin "P$5") (pinfunction "P01_P$5") (pintype "bidirectional"))
      (node (ref "U12") (pin "P$4") (pinfunction "STAT_P$4") (pintype "bidirectional"))
    )
    (net (code "14") (name "L1_TEMP") (class "Default")
      (node (ref "T1") (pin "-") (pinfunction "-_-") (pintype "bidirectional"))
      (node (ref "V8") (pin "P$1") (pinfunction "P$1_P$1") (pintype "bidirectional"))
    )
    (net (code "15") (name "L2_CHG") (class "Default")
      (node (ref "R1") (pin "2") (pinfunction "2_2") (pintype "passive"))
      (node (ref "R36") (pin "2") (pinfunction "2_2") (pintype "passive"))
      (node (ref "U5") (pin "P$16") (pinfunction "RUN_P$16") (pintype "bidirectional"))
      (node (ref "V33") (pin "P$1") (pinfunction "P$1_P$1") (pintype "bidirectional"))
    )
    (net (code "16") (name "L2_CHGN") (class "Default")
      (node (ref "R2") (pin "1") (pinfunction "1_1") (pintype "passive"))
      (node (ref "U1") (pin "P$10") (pinfunction "P06_P$10") (pintype "bidirectional"))
      (node (ref "U5") (pin "P$14") (pinfunction "~{CHRG}_P$14") (pintype "bidirectional"))
    )
    (net (code "17") (name "L2_DISG") (class "Default")
      (node (ref "U13") (pin "P$3") (pinfunction "CNTRL_P$3") (pintype "bidirectional"))
      (node (ref "V30") (pin "P$1") (pinfunction "P$1_P$1") (pintype "bidirectional"))
    )
    (net (code "18") (name "L2_FAULTN") (class "Default")
      (node (ref "R3") (pin "1") (pinfunction "1_1") (pintype "passive"))
      (node (ref "U1") (pin "P$11") (pinfunction "P07_P$11") (pintype "bidirectional"))
      (node (ref "U5") (pin "P$15") (pinfunction "~{FAULT}_P$15") (pintype "bidirectional"))
    )
    (net (code "19") (name "L2_PROG") (class "Default")
      (node (ref "R9") (pin "2") (pinfunction "2_2") (pintype "passive"))
      (node (ref "U5") (pin "P$13") (pinfunction "PROG_P$13") (pintype "bidirectional"))
    )
    (net (code "20") (name "L2_REF") (class "Default")
      (node (ref "R16") (pin "1") (pinfunction "1_1") (pintype "passive"))
      (node (ref "R19") (pin "2") (pinfunction "2_2") (pintype "passive"))
      (node (ref "V31") (pin "P$1") (pinfunction "P$1_P$1") (pintype "bidirectional"))
    )
    (net (code "21") (name "L2_SNS") (class "Default")
      (node (ref "U2") (pin "P$3") (pinfunction "VIN0_P$3") (pintype "bidirectional"))
      (node (ref "U9") (pin "P$5") (pinfunction "OUT_P$5") (pintype "bidirectional"))
    )
    (net (code "22") (name "L2_SNS+") (class "Default")
      (node (ref "LI-ION2") (pin "MINUS") (pinfunction "MINUS_MINUS") (pintype "power_in"))
      (node (ref "R12") (pin "P$2") (pinfunction "2_P$2") (pintype "passive"))
      (node (ref "U9") (pin "P$8") (pinfunction "+IN_P$8") (pintype "bidirectional"))
    )
    (net (code "23") (name "L2_SNS-") (class "Default")
      (node (ref "R12") (pin "P$1") (pinfunction "1_P$1") (pintype "passive"))
      (node (ref "U9") (pin "P$1") (pinfunction "-IN_P$1") (pintype "bidirectional"))
      (node (ref "V24") (pin "P$1") (pinfunction "P$1_P$1") (pintype "bidirectional"))
    )
    (net (code "24") (name "L2_ST") (class "Default")
      (node (ref "R38") (pin "1") (pinfunction "1_1") (pintype "passive"))
      (node (ref "U1") (pin "P$4") (pinfunction "P00_P$4") (pintype "bidirectional"))
      (node (ref "U13") (pin "P$4") (pinfunction "STAT_P$4") (pintype "bidirectional"))
    )
    (net (code "25") (name "L2_TEMP") (class "Default")
      (node (ref "T2") (pin "-") (pinfunction "-_-") (pintype "bidirectional"))
      (node (ref "V9") (pin "P$1") (pinfunction "P$1_P$1") (pintype "bidirectional"))
    )
    (net (code "26") (name "LF1_REF") (class "Default")
      (node (ref "R49") (pin "2") (pinfunction "2_2") (pintype "passive"))
      (node (ref "R50") (pin "2") (pinfunction "2_2") (pintype "passive"))
      (node (ref "V41") (pin "P$1") (pinfunction "P$1_P$1") (pintype "bidirectional"))
    )
    (net (code "27") (name "LF1_TEMP") (class "Default")
      (node (ref "T3") (pin "-") (pinfunction "-_-") (pintype "bidirectional"))
      (node (ref "V10") (pin "P$1") (pinfunction "P$1_P$1") (pintype "bidirectional"))
    )
    (net (code "28") (name "LF2_REF") (class "Default")
      (node (ref "R47") (pin "1") (pinfunction "1_1") (pintype "passive"))
      (node (ref "R48") (pin "2") (pinfunction "2_2") (pintype "passive"))
      (node (ref "V42") (pin "P$1") (pinfunction "P$1_P$1") (pintype "bidirectional"))
    )
    (net (code "29") (name "LF3_REF") (class "Default")
      (node (ref "R67") (pin "2") (pinfunction "2_2") (pintype "passive"))
      (node (ref "R68") (pin "2") (pinfunction "2_2") (pintype "passive"))
      (node (ref "V49") (pin "P$1") (pinfunction "P$1_P$1") (pintype "bidirectional"))
    )
    (net (code "30") (name "LF3_TEMP") (class "Default")
      (node (ref "T4") (pin "-") (pinfunction "-_-") (pintype "bidirectional"))
      (node (ref "V11") (pin "P$1") (pinfunction "P$1_P$1") (pintype "bidirectional"))
    )
    (net (code "31") (name "LF4_REF") (class "Default")
      (node (ref "R65") (pin "1") (pinfunction "1_1") (pintype "passive"))
      (node (ref "R66") (pin "2") (pinfunction "2_2") (pintype "passive"))
      (node (ref "V50") (pin "P$1") (pinfunction "P$1_P$1") (pintype "bidirectional"))
    )
    (net (code "32") (name "LFB1_SNS+") (class "Default")
      (node (ref "LIFEPO42") (pin "MINUS") (pinfunction "MINUS_MINUS") (pintype "power_in"))
      (node (ref "R41") (pin "P$2") (pinfunction "2_P$2") (pintype "passive"))
      (node (ref "U18") (pin "P$8") (pinfunction "+IN_P$8") (pintype "bidirectional"))
    )
    (net (code "33") (name "LFB2_SNS+") (class "Default")
      (node (ref "LIFEPO44") (pin "MINUS") (pinfunction "MINUS_MINUS") (pintype "power_in"))
      (node (ref "R59") (pin "P$2") (pinfunction "2_P$2") (pintype "passive"))
      (node (ref "U19") (pin "P$8") (pinfunction "+IN_P$8") (pintype "bidirectional"))
    )
    (net (code "34") (name "LF_B1") (class "Default")
      (node (ref "C30") (pin "1") (pinfunction "P$1_1") (pintype "passive"))
      (node (ref "SW1") (pin "P$5") (pinfunction "OUT_P$5") (pintype "power_in"))
      (node (ref "SW1") (pin "P$6") (pinfunction "OUT_P$6") (pintype "power_in"))
      (node (ref "SW1") (pin "P$7") (pinfunction "OUT_P$7") (pintype "power_in"))
      (node (ref "V45") (pin "P$1") (pinfunction "P$1_P$1") (pintype "bidirectional"))
    )
    (net (code "35") (name "LF_B1_BT") (class "Default")
      (node (ref "R57") (pin "2") (pinfunction "2_2") (pintype "passive"))
      (node (ref "U1") (pin "P$16") (pinfunction "P13_P$16") (pintype "bidirectional"))
      (node (ref "U15") (pin "P$4") (pinfunction "G2_P$4") (pintype "bidirectional"))
    )
    (net (code "36") (name "LF_B1_CHG") (class "Default")
      (node (ref "R44") (pin "2") (pinfunction "2_2") (pintype "passive"))
      (node (ref "U14") (pin "P$16") (pinfunction "RUN_P$16") (pintype "bidirectional"))
      (node (ref "V32") (pin "P$1") (pinfunction "P$1_P$1") (pintype "bidirectional"))
      (node (ref "V35") (pin "P$1") (pinfunction "P$1_P$1") (pintype "bidirectional"))
    )
    (net (code "37") (name "LF_B1_CHGN") (class "Default")
      (node (ref "R42") (pin "1") (pinfunction "1_1") (pintype "passive"))
      (node (ref "U1") (pin "P$20") (pinfunction "P17_P$20") (pintype "bidirectional"))
      (node (ref "U14") (pin "P$14") (pinfunction "~{CHRG}_P$14") (pintype "bidirectional"))
    )
    (net (code "38") (name "LF_B1_FAULTN") (class "Default")
      (node (ref "R43") (pin "1") (pinfunction "1_1") (pintype "passive"))
      (node (ref "U1") (pin "P$19") (pinfunction "P16_P$19") (pintype "bidirectional"))
      (node (ref "U14") (pin "P$15") (pinfunction "~{FAULT}_P$15") (pintype "bidirectional"))
    )
    (net (code "39") (name "LF_B1_OSNS") (class "Default")
      (node (ref "C31") (pin "1") (pinfunction "P$1_1") (pintype "passive"))
      (node (ref "R79") (pin "1") (pinfunction "1_1") (pintype "passive"))
      (node (ref "V46") (pin "P$1") (pinfunction "P$1_P$1") (pintype "bidirectional"))
    )
    (net (code "40") (name "LF_B1_OUTEN") (class "Default")
      (node (ref "R78") (pin "1") (pinfunction "1_1") (pintype "passive"))
      (node (ref "V43") (pin "P$1") (pinfunction "P$1_P$1") (pintype "bidirectional"))
    )
    (net (code "41") (name "LF_B1_SNS") (class "Default")
      (node (ref "U18") (pin "P$5") (pinfunction "OUT_P$5") (pintype "bidirectional"))
      (node (ref "V40") (pin "P$1") (pinfunction "P$1_P$1") (pintype "bidirectional"))
    )
    (net (code "42") (name "LF_B1_TT") (class "Default")
      (node (ref "R56") (pin "2") (pinfunction "2_2") (pintype "passive"))
      (node (ref "U1") (pin "P$15") (pinfunction "P12_P$15") (pintype "bidirectional"))
      (node (ref "U15") (pin "P$2") (pinfunction "G1_P$2") (pintype "bidirectional"))
    )
    (net (code "43") (name "LF_B2") (class "Default")
      (node (ref "C37") (pin "1") (pinfunction "P$1_1") (pintype "passive"))
      (node (ref "SW2") (pin "P$5") (pinfunction "OUT_P$5") (pintype "power_in"))
      (node (ref "SW2") (pin "P$6") (pinfunction "OUT_P$6") (pintype "power_in"))
      (node (ref "SW2") (pin "P$7") (pinfunction "OUT_P$7") (pintype "power_in"))
      (node (ref "V53") (pin "P$1") (pinfunction "P$1_P$1") (pintype "bidirectional"))
    )
    (net (code "44") (name "LF_B2_BT") (class "Default")
      (node (ref "R75") (pin "2") (pinfunction "2_2") (pintype "passive"))
      (node (ref "U1") (pin "P$13") (pinfunction "P10_P$13") (pintype "bidirectional"))
      (node (ref "U17") (pin "P$4") (pinfunction "G2_P$4") (pintype "bidirectional"))
    )
    (net (code "45") (name "LF_B2_CHG") (class "Default")
      (node (ref "R62") (pin "2") (pinfunction "2_2") (pintype "passive"))
      (node (ref "U16") (pin "P$16") (pinfunction "RUN_P$16") (pintype "bidirectional"))
      (node (ref "V47") (pin "P$1") (pinfunction "P$1_P$1") (pintype "bidirectional"))
    )
    (net (code "46") (name "LF_B2_CHGN") (class "Default")
      (node (ref "R60") (pin "1") (pinfunction "1_1") (pintype "passive"))
      (node (ref "U1") (pin "P$17") (pinfunction "P14_P$17") (pintype "bidirectional"))
      (node (ref "U16") (pin "P$14") (pinfunction "~{CHRG}_P$14") (pintype "bidirectional"))
    )
    (net (code "47") (name "LF_B2_FAULTN") (class "Default")
      (node (ref "R61") (pin "1") (pinfunction "1_1") (pintype "passive"))
      (node (ref "U1") (pin "P$18") (pinfunction "P15_P$18") (pintype "bidirectional"))
      (node (ref "U16") (pin "P$15") (pinfunction "~{FAULT}_P$15") (pintype "bidirectional"))
    )
    (net (code "48") (name "LF_B2_OSNS") (class "Default")
      (node (ref "C38") (pin "1") (pinfunction "P$1_1") (pintype "passive"))
      (node (ref "R82") (pin "1") (pinfunction "1_1") (pintype "passive"))
      (node (ref "V99") (pin "P$1") (pinfunction "P$1_P$1") (pintype "bidirectional"))
    )
    (net (code "49") (name "LF_B2_OUTEN") (class "Default")
      (node (ref "R81") (pin "1") (pinfunction "1_1") (pintype "passive"))
      (node (ref "V51") (pin "P$1") (pinfunction "P$1_P$1") (pintype "bidirectional"))
    )
    (net (code "50") (name "LF_B2_SNS") (class "Default")
      (node (ref "U19") (pin "P$5") (pinfunction "OUT_P$5") (pintype "bidirectional"))
      (node (ref "V44") (pin "P$1") (pinfunction "P$1_P$1") (pintype "bidirectional"))
    )
    (net (code "51") (name "LF_B2_TT") (class "Default")
      (node (ref "R74") (pin "2") (pinfunction "2_2") (pintype "passive"))
      (node (ref "U1") (pin "P$14") (pinfunction "P11_P$14") (pintype "bidirectional"))
      (node (ref "U17") (pin "P$2") (pinfunction "G1_P$2") (pintype "bidirectional"))
    )
    (net (code "52") (name "LIFE1") (class "Default")
      (node (ref "C28") (pin "1") (pinfunction "P$1_1") (pintype "passive"))
      (node (ref "D4") (pin "C") (pinfunction "C_C") (pintype "passive"))
      (node (ref "F3") (pin "P$1") (pinfunction "P$1_P$1") (pintype "passive"))
      (node (ref "F4") (pin "P$1") (pinfunction "P$1_P$1") (pintype "passive"))
      (node (ref "LIFEPO41") (pin "PLUS") (pinfunction "PLUS_PLUS") (pintype "power_in"))
      (node (ref "R49") (pin "1") (pinfunction "1_1") (pintype "passive"))
      (node (ref "R53") (pin "2") (pinfunction "2_2") (pintype "passive"))
      (node (ref "R54") (pin "P$2") (pinfunction "2_P$2") (pintype "passive"))
      (node (ref "U14") (pin "P$9") (pinfunction "BAT_P$9") (pintype "bidirectional"))
    )
    (net (code "53") (name "LIFE1FUSEOUT") (class "Default")
      (node (ref "F3") (pin "P$2") (pinfunction "P$2_P$2") (pintype "passive"))
      (node (ref "F4") (pin "P$2") (pinfunction "P$2_P$2") (pintype "passive"))
      (node (ref "SW1") (pin "PAD") (pinfunction "VB_PAD") (pintype "power_in"))
    )
    (net (code "54") (name "LIFE3") (class "Default")
      (node (ref "C35") (pin "1") (pinfunction "P$1_1") (pintype "passive"))
      (node (ref "D5") (pin "C") (pinfunction "C_C") (pintype "passive"))
      (node (ref "F5") (pin "P$1") (pinfunction "P$1_P$1") (pintype "passive"))
      (node (ref "F6") (pin "P$1") (pinfunction "P$1_P$1") (pintype "passive"))
      (node (ref "LIFEPO43") (pin "PLUS") (pinfunction "PLUS_PLUS") (pintype "power_in"))
      (node (ref "R67") (pin "1") (pinfunction "1_1") (pintype "passive"))
      (node (ref "R71") (pin "2") (pinfunction "2_2") (pintype "passive"))
      (node (ref "R72") (pin "P$2") (pinfunction "2_P$2") (pintype "passive"))
      (node (ref "U16") (pin "P$9") (pinfunction "BAT_P$9") (pintype "bidirectional"))
    )
    (net (code "55") (name "LIFE3FUSEOUT") (class "Default")
      (node (ref "F5") (pin "P$2") (pinfunction "P$2_P$2") (pintype "passive"))
      (node (ref "F6") (pin "P$2") (pinfunction "P$2_P$2") (pintype "passive"))
      (node (ref "SW2") (pin "PAD") (pinfunction "VB_PAD") (pintype "power_in"))
    )
    (net (code "56") (name "LION1") (class "Default")
      (node (ref "C11") (pin "1") (pinfunction "P$1_1") (pintype "passive"))
      (node (ref "F1") (pin "1") (pinfunction "P$1_1") (pintype "passive"))
      (node (ref "LI-ION1") (pin "PLUS") (pinfunction "PLUS_PLUS") (pintype "power_in"))
      (node (ref "R33") (pin "2") (pinfunction "2_2") (pintype "passive"))
      (node (ref "R7") (pin "2") (pinfunction "2_2") (pintype "passive"))
      (node (ref "U4") (pin "P$10") (pinfunction "BATSNS_P$10") (pintype "bidirectional"))
      (node (ref "U4") (pin "P$9") (pinfunction "BAT_P$9") (pintype "bidirectional"))
    )
    (net (code "57") (name "LION1_OUT") (class "Default")
      (node (ref "C15") (pin "2") (pinfunction "P$2_2") (pintype "passive"))
      (node (ref "F1") (pin "2") (pinfunction "P$2_2") (pintype "passive"))
      (node (ref "U12") (pin "P$1") (pinfunction "IN_P$1") (pintype "bidirectional"))
    )
    (net (code "58") (name "LION2") (class "Default")
      (node (ref "C12") (pin "1") (pinfunction "P$1_1") (pintype "passive"))
      (node (ref "F2") (pin "1") (pinfunction "P$1_1") (pintype "passive"))
      (node (ref "LI-ION2") (pin "PLUS") (pinfunction "PLUS_PLUS") (pintype "power_in"))
      (node (ref "R16") (pin "2") (pinfunction "2_2") (pintype "passive"))
      (node (ref "R22") (pin "2") (pinfunction "2_2") (pintype "passive"))
      (node (ref "U5") (pin "P$10") (pinfunction "BATSNS_P$10") (pintype "bidirectional"))
      (node (ref "U5") (pin "P$9") (pinfunction "BAT_P$9") (pintype "bidirectional"))
    )
    (net (code "59") (name "LION2_OUT") (class "Default")
      (node (ref "C16") (pin "2") (pinfunction "P$2_2") (pintype "passive"))
      (node (ref "F2") (pin "2") (pinfunction "P$2_2") (pintype "passive"))
      (node (ref "U13") (pin "P$1") (pinfunction "IN_P$1") (pintype "bidirectional"))
    )
    (net (code "60") (name "L_OUT") (class "Default")
      (node (ref "C21") (pin "1") (pinfunction "P$1_1") (pintype "passive"))
      (node (ref "C22") (pin "1") (pinfunction "P$1_1") (pintype "passive"))
      (node (ref "D2") (pin "C") (pinfunction "C_C") (pintype "bidirectional"))
      (node (ref "D3") (pin "C") (pinfunction "C_C") (pintype "bidirectional"))
      (node (ref "R37") (pin "2") (pinfunction "2_2") (pintype "passive"))
      (node (ref "R38") (pin "2") (pinfunction "2_2") (pintype "passive"))
      (node (ref "R39") (pin "2") (pinfunction "2_2") (pintype "passive"))
      (node (ref "U12") (pin "P$5") (pinfunction "OUT_P$5") (pintype "bidirectional"))
      (node (ref "U13") (pin "P$5") (pinfunction "OUT_P$5") (pintype "bidirectional"))
      (node (ref "V34") (pin "P$1") (pinfunction "P$1_P$1") (pintype "bidirectional"))
    )
    (net (code "61") (name "L_REF") (class "Default")
      (node (ref "R39") (pin "1") (pinfunction "1_1") (pintype "passive"))
      (node (ref "R40") (pin "2") (pinfunction "2_2") (pintype "passive"))
      (node (ref "U2") (pin "P$5") (pinfunction "VIN2_P$5") (pintype "bidirectional"))
    )
    (net (code "62") (name "Net-(C7-P$1)") (class "Default")
      (node (ref "C7") (pin "1") (pinfunction "P$1_1") (pintype "passive"))
      (node (ref "U4") (pin "P$1") (pinfunction "INTVCC_P$1") (pintype "bidirectional"))
    )
    (net (code "63") (name "Net-(C8-P$1)") (class "Default")
      (node (ref "C8") (pin "1") (pinfunction "P$1_1") (pintype "passive"))
      (node (ref "U5") (pin "P$1") (pinfunction "INTVCC_P$1") (pintype "bidirectional"))
    )
    (net (code "64") (name "Net-(C9-P$1)") (class "Default")
      (node (ref "C9") (pin "1") (pinfunction "P$1_1") (pintype "passive"))
      (node (ref "U4") (pin "P$2") (pinfunction "BOOST_P$2") (pintype "bidirectional"))
    )
    (net (code "65") (name "Net-(C9-P$2)") (class "Default")
      (node (ref "C9") (pin "2") (pinfunction "P$2_2") (pintype "passive"))
      (node (ref "L1") (pin "P$1") (pinfunction "P$1_P$1") (pintype "passive"))
      (node (ref "U4") (pin "P$4") (pinfunction "SW_P$4") (pintype "bidirectional"))
    )
    (net (code "66") (name "Net-(C10-P$1)") (class "Default")
      (node (ref "C10") (pin "1") (pinfunction "P$1_1") (pintype "passive"))
      (node (ref "U5") (pin "P$2") (pinfunction "BOOST_P$2") (pintype "bidirectional"))
    )
    (net (code "67") (name "Net-(C10-P$2)") (class "Default")
      (node (ref "C10") (pin "2") (pinfunction "P$2_2") (pintype "passive"))
      (node (ref "L2") (pin "P$1") (pinfunction "P$1_P$1") (pintype "passive"))
      (node (ref "U5") (pin "P$4") (pinfunction "SW_P$4") (pintype "bidirectional"))
    )
    (net (code "68") (name "Net-(C13-P$2)") (class "Default")
      (node (ref "C13") (pin "2") (pinfunction "P$2_2") (pintype "passive"))
      (node (ref "R7") (pin "1") (pinfunction "1_1") (pintype "passive"))
      (node (ref "U6") (pin "P$5") (pinfunction "VCC_P$5") (pintype "bidirectional"))
    )
    (net (code "69") (name "Net-(C14-P$2)") (class "Default")
      (node (ref "C14") (pin "2") (pinfunction "P$2_2") (pintype "passive"))
      (node (ref "R22") (pin "1") (pinfunction "1_1") (pintype "passive"))
      (node (ref "U7") (pin "P$5") (pinfunction "VCC_P$5") (pintype "bidirectional"))
    )
    (net (code "70") (name "Net-(C19-P$1)") (class "Default")
      (node (ref "C19") (pin "1") (pinfunction "P$1_1") (pintype "passive"))
      (node (ref "C23") (pin "1") (pinfunction "P$1_1") (pintype "passive"))
      (node (ref "D2") (pin "A") (pinfunction "A_A") (pintype "bidirectional"))
      (node (ref "U10") (pin "P$1") (pinfunction "OUT_P$1") (pintype "bidirectional"))
      (node (ref "U10") (pin "P$2") (pinfunction "SENSE_P$2") (pintype "bidirectional"))
    )
    (net (code "71") (name "Net-(C19-P$2)") (class "Default")
      (node (ref "C19") (pin "2") (pinfunction "P$2_2") (pintype "passive"))
      (node (ref "U10") (pin "P$3") (pinfunction "BYP_P$3") (pintype "bidirectional"))
    )
    (net (code "72") (name "Net-(C20-P$1)") (class "Default")
      (node (ref "C20") (pin "1") (pinfunction "P$1_1") (pintype "passive"))
      (node (ref "C24") (pin "1") (pinfunction "P$1_1") (pintype "passive"))
      (node (ref "D3") (pin "A") (pinfunction "A_A") (pintype "bidirectional"))
      (node (ref "U11") (pin "P$1") (pinfunction "OUT_P$1") (pintype "bidirectional"))
      (node (ref "U11") (pin "P$2") (pinfunction "SENSE_P$2") (pintype "bidirectional"))
    )
    (net (code "73") (name "Net-(C20-P$2)") (class "Default")
      (node (ref "C20") (pin "2") (pinfunction "P$2_2") (pintype "passive"))
      (node (ref "U11") (pin "P$3") (pinfunction "BYP_P$3") (pintype "bidirectional"))
    )
    (net (code "74") (name "Net-(C26-P$2)") (class "Default")
      (node (ref "C26") (pin "2") (pinfunction "P$2_2") (pintype "passive"))
      (node (ref "U14") (pin "P$1") (pinfunction "INTVCC_P$1") (pintype "bidirectional"))
    )
    (net (code "75") (name "Net-(C27-P$1)") (class "Default")
      (node (ref "C27") (pin "1") (pinfunction "P$1_1") (pintype "passive"))
      (node (ref "L3") (pin "P$2") (pinfunction "P$2_P$2") (pintype "passive"))
      (node (ref "U14") (pin "P$4") (pinfunction "SW_P$4") (pintype "bidirectional"))
    )
    (net (code "76") (name "Net-(C27-P$2)") (class "Default")
      (node (ref "C27") (pin "2") (pinfunction "P$2_2") (pintype "passive"))
      (node (ref "U14") (pin "P$2") (pinfunction "BOOST_P$2") (pintype "bidirectional"))
    )
    (net (code "77") (name "Net-(C29-P$2)") (class "Default")
      (node (ref "C29") (pin "2") (pinfunction "P$2_2") (pintype "passive"))
      (node (ref "R77") (pin "2") (pinfunction "2_2") (pintype "passive"))
      (node (ref "R78") (pin "2") (pinfunction "2_2") (pintype "passive"))
      (node (ref "SW1") (pin "P$2") (pinfunction "CNTRL_P$2") (pintype "input"))
    )
    (net (code "78") (name "Net-(C33-P$2)") (class "Default")
      (node (ref "C33") (pin "2") (pinfunction "P$2_2") (pintype "passive"))
      (node (ref "U16") (pin "P$1") (pinfunction "INTVCC_P$1") (pintype "bidirectional"))
    )
    (net (code "79") (name "Net-(C34-P$1)") (class "Default")
      (node (ref "C34") (pin "1") (pinfunction "P$1_1") (pintype "passive"))
      (node (ref "L4") (pin "P$2") (pinfunction "P$2_P$2") (pintype "passive"))
      (node (ref "U16") (pin "P$4") (pinfunction "SW_P$4") (pintype "bidirectional"))
    )
    (net (code "80") (name "Net-(C34-P$2)") (class "Default")
      (node (ref "C34") (pin "2") (pinfunction "P$2_2") (pintype "passive"))
      (node (ref "U16") (pin "P$2") (pinfunction "BOOST_P$2") (pintype "bidirectional"))
    )
    (net (code "81") (name "Net-(C36-P$2)") (class "Default")
      (node (ref "C36") (pin "2") (pinfunction "P$2_2") (pintype "passive"))
      (node (ref "R80") (pin "2") (pinfunction "2_2") (pintype "passive"))
      (node (ref "R81") (pin "2") (pinfunction "2_2") (pintype "passive"))
      (node (ref "SW2") (pin "P$2") (pinfunction "CNTRL_P$2") (pintype "input"))
    )
    (net (code "82") (name "Net-(M1-G)") (class "Default")
      (node (ref "M1") (pin "P$4") (pinfunction "G_P$4") (pintype "bidirectional"))
      (node (ref "U3") (pin "P$5") (pinfunction "GATE_P$5") (pintype "bidirectional"))
    )
    (net (code "83") (name "Net-(R54-1)") (class "Default")
      (node (ref "R54") (pin "P$1") (pinfunction "1_P$1") (pintype "passive"))
      (node (ref "U15") (pin "P$7") (pinfunction "D1_P$7") (pintype "bidirectional"))
      (node (ref "U15") (pin "P$8") (pinfunction "D1_P$8") (pintype "bidirectional"))
    )
    (net (code "84") (name "Net-(R55-1)") (class "Default")
      (node (ref "LIFEPO41") (pin "MINUS") (pinfunction "MINUS_MINUS") (pintype "power_in"))
      (node (ref "LIFEPO42") (pin "PLUS") (pinfunction "PLUS_PLUS") (pintype "power_in"))
      (node (ref "R47") (pin "2") (pinfunction "2_2") (pintype "passive"))
      (node (ref "R55") (pin "P$1") (pinfunction "1_P$1") (pintype "passive"))
      (node (ref "U15") (pin "P$1") (pinfunction "S1_P$1") (pintype "bidirectional"))
    )
    (net (code "85") (name "Net-(R55-2)") (class "Default")
      (node (ref "R55") (pin "P$2") (pinfunction "2_P$2") (pintype "passive"))
      (node (ref "U15") (pin "P$5") (pinfunction "D2_P$5") (pintype "bidirectional"))
      (node (ref "U15") (pin "P$6") (pinfunction "D2_P$6") (pintype "bidirectional"))
    )
    (net (code "86") (name "Net-(R72-1)") (class "Default")
      (node (ref "R72") (pin "P$1") (pinfunction "1_P$1") (pintype "passive"))
      (node (ref "U17") (pin "P$7") (pinfunction "D1_P$7") (pintype "bidirectional"))
      (node (ref "U17") (pin "P$8") (pinfunction "D1_P$8") (pintype "bidirectional"))
    )
    (net (code "87") (name "Net-(R73-1)") (class "Default")
      (node (ref "LIFEPO43") (pin "MINUS") (pinfunction "MINUS_MINUS") (pintype "power_in"))
      (node (ref "LIFEPO44") (pin "PLUS") (pinfunction "PLUS_PLUS") (pintype "power_in"))
      (node (ref "R65") (pin "2") (pinfunction "2_2") (pintype "passive"))
      (node (ref "R73") (pin "P$1") (pinfunction "1_P$1") (pintype "passive"))
      (node (ref "U17") (pin "P$1") (pinfunction "S1_P$1") (pintype "bidirectional"))
    )
    (net (code "88") (name "Net-(R73-2)") (class "Default")
      (node (ref "R73") (pin "P$2") (pinfunction "2_P$2") (pintype "passive"))
      (node (ref "U17") (pin "P$5") (pinfunction "D2_P$5") (pintype "bidirectional"))
      (node (ref "U17") (pin "P$6") (pinfunction "D2_P$6") (pintype "bidirectional"))
    )
    (net (code "89") (name "Net-(SW1-ISNS)") (class "Default")
      (node (ref "R58") (pin "2") (pinfunction "2_2") (pintype "passive"))
      (node (ref "R79") (pin "2") (pinfunction "2_2") (pintype "passive"))
      (node (ref "SW1") (pin "P$3") (pinfunction "ISNS_P$3") (pintype "output"))
    )
    (net (code "90") (name "Net-(SW2-ISNS)") (class "Default")
      (node (ref "R76") (pin "2") (pinfunction "2_2") (pintype "passive"))
      (node (ref "R82") (pin "2") (pinfunction "2_2") (pintype "passive"))
      (node (ref "SW2") (pin "P$3") (pinfunction "ISNS_P$3") (pintype "output"))
    )
    (net (code "91") (name "Net-(U1-P03)") (class "Default")
      (node (ref "R32") (pin "2") (pinfunction "2_2") (pintype "passive"))
      (node (ref "U1") (pin "P$7") (pinfunction "P03_P$7") (pintype "bidirectional"))
    )
    (net (code "92") (name "Net-(U4-CHGSNS)") (class "Default")
      (node (ref "L1") (pin "P$2") (pinfunction "P$2_P$2") (pintype "passive"))
      (node (ref "U4") (pin "P$8") (pinfunction "CHGSNS_P$8") (pintype "bidirectional"))
    )
    (net (code "93") (name "Net-(U4-MPPT)") (class "Default")
      (node (ref "R27") (pin "1") (pinfunction "1_1") (pintype "passive"))
      (node (ref "R28") (pin "2") (pinfunction "2_2") (pintype "passive"))
      (node (ref "U4") (pin "P$6") (pinfunction "MPPT_P$6") (pintype "bidirectional"))
    )
    (net (code "94") (name "Net-(U5-CHGSNS)") (class "Default")
      (node (ref "L2") (pin "P$2") (pinfunction "P$2_P$2") (pintype "passive"))
      (node (ref "U5") (pin "P$8") (pinfunction "CHGSNS_P$8") (pintype "bidirectional"))
    )
    (net (code "95") (name "Net-(U5-MPPT)") (class "Default")
      (node (ref "R10") (pin "1") (pinfunction "1_1") (pintype "passive"))
      (node (ref "R11") (pin "2") (pinfunction "2_2") (pintype "passive"))
      (node (ref "U5") (pin "P$6") (pinfunction "MPPT_P$6") (pintype "bidirectional"))
    )
    (net (code "96") (name "Net-(U6-CS)") (class "Default")
      (node (ref "R8") (pin "2") (pinfunction "2_2") (pintype "passive"))
      (node (ref "U6") (pin "P$2") (pinfunction "CS_P$2") (pintype "bidirectional"))
    )
    (net (code "97") (name "Net-(U6-S1)") (class "Default")
      (node (ref "U6") (pin "P$6") (pinfunction "S1_P$6") (pintype "bidirectional"))
      (node (ref "V23") (pin "P$1") (pinfunction "P$1_P$1") (pintype "bidirectional"))
    )
    (net (code "98") (name "Net-(U7-CS)") (class "Default")
      (node (ref "R23") (pin "2") (pinfunction "2_2") (pintype "passive"))
      (node (ref "U7") (pin "P$2") (pinfunction "CS_P$2") (pintype "bidirectional"))
    )
    (net (code "99") (name "Net-(U7-S1)") (class "Default")
      (node (ref "U7") (pin "P$6") (pinfunction "S1_P$6") (pintype "bidirectional"))
      (node (ref "V25") (pin "P$1") (pinfunction "P$1_P$1") (pintype "bidirectional"))
    )
    (net (code "100") (name "Net-(U8-VREF1)") (class "Default")
      (node (ref "R4") (pin "2") (pinfunction "2_2") (pintype "passive"))
      (node (ref "R6") (pin "1") (pinfunction "1_1") (pintype "passive"))
      (node (ref "U8") (pin "P$3") (pinfunction "VREF2_P$3") (pintype "bidirectional"))
      (node (ref "U8") (pin "P$7") (pinfunction "VREF1_P$7") (pintype "bidirectional"))
    )
    (net (code "101") (name "Net-(U9-VREF1)") (class "Default")
      (node (ref "R20") (pin "2") (pinfunction "2_2") (pintype "passive"))
      (node (ref "R21") (pin "1") (pinfunction "1_1") (pintype "passive"))
      (node (ref "U9") (pin "P$3") (pinfunction "VREF2_P$3") (pintype "bidirectional"))
      (node (ref "U9") (pin "P$7") (pinfunction "VREF1_P$7") (pintype "bidirectional"))
    )
    (net (code "102") (name "Net-(U14-CHGSNS)") (class "Default")
      (node (ref "L3") (pin "P$1") (pinfunction "P$1_P$1") (pintype "passive"))
      (node (ref "U14") (pin "P$8") (pinfunction "CHGSNS_P$8") (pintype "bidirectional"))
    )
    (net (code "103") (name "Net-(U14-FB)") (class "Default")
      (node (ref "R52") (pin "2") (pinfunction "2_2") (pintype "passive"))
      (node (ref "R53") (pin "1") (pinfunction "1_1") (pintype "passive"))
      (node (ref "U14") (pin "P$10") (pinfunction "FB_P$10") (pintype "bidirectional"))
    )
    (net (code "104") (name "Net-(U14-FBG)") (class "Default")
      (node (ref "R52") (pin "1") (pinfunction "1_1") (pintype "passive"))
      (node (ref "U14") (pin "P$11") (pinfunction "FBG_P$11") (pintype "bidirectional"))
    )
    (net (code "105") (name "Net-(U14-MPPT)") (class "Default")
      (node (ref "R45") (pin "1") (pinfunction "1_1") (pintype "passive"))
      (node (ref "R46") (pin "2") (pinfunction "2_2") (pintype "passive"))
      (node (ref "U14") (pin "P$6") (pinfunction "MPPT_P$6") (pintype "bidirectional"))
    )
    (net (code "106") (name "Net-(U14-PROG)") (class "Default")
      (node (ref "R51") (pin "1") (pinfunction "1_1") (pintype "passive"))
      (node (ref "U14") (pin "P$13") (pinfunction "PROG_P$13") (pintype "bidirectional"))
    )
    (net (code "107") (name "Net-(U16-CHGSNS)") (class "Default")
      (node (ref "L4") (pin "P$1") (pinfunction "P$1_P$1") (pintype "passive"))
      (node (ref "U16") (pin "P$8") (pinfunction "CHGSNS_P$8") (pintype "bidirectional"))
    )
    (net (code "108") (name "Net-(U16-FB)") (class "Default")
      (node (ref "R70") (pin "2") (pinfunction "2_2") (pintype "passive"))
      (node (ref "R71") (pin "1") (pinfunction "1_1") (pintype "passive"))
      (node (ref "U16") (pin "P$10") (pinfunction "FB_P$10") (pintype "bidirectional"))
    )
    (net (code "109") (name "Net-(U16-FBG)") (class "Default")
      (node (ref "R70") (pin "1") (pinfunction "1_1") (pintype "passive"))
      (node (ref "U16") (pin "P$11") (pinfunction "FBG_P$11") (pintype "bidirectional"))
    )
    (net (code "110") (name "Net-(U16-MPPT)") (class "Default")
      (node (ref "R63") (pin "1") (pinfunction "1_1") (pintype "passive"))
      (node (ref "R64") (pin "2") (pinfunction "2_2") (pintype "passive"))
      (node (ref "U16") (pin "P$6") (pinfunction "MPPT_P$6") (pintype "bidirectional"))
    )
    (net (code "111") (name "Net-(U16-PROG)") (class "Default")
      (node (ref "R69") (pin "1") (pinfunction "1_1") (pintype "passive"))
      (node (ref "U16") (pin "P$13") (pinfunction "PROG_P$13") (pintype "bidirectional"))
    )
    (net (code "112") (name "Net-(U18-VREF1)") (class "Default")
      (node (ref "R24") (pin "2") (pinfunction "2_2") (pintype "passive"))
      (node (ref "R26") (pin "1") (pinfunction "1_1") (pintype "passive"))
      (node (ref "U18") (pin "P$3") (pinfunction "VREF2_P$3") (pintype "bidirectional"))
      (node (ref "U18") (pin "P$7") (pinfunction "VREF1_P$7") (pintype "bidirectional"))
    )
    (net (code "113") (name "Net-(U19-VREF1)") (class "Default")
      (node (ref "R29") (pin "2") (pinfunction "2_2") (pintype "passive"))
      (node (ref "R30") (pin "1") (pinfunction "1_1") (pintype "passive"))
      (node (ref "U19") (pin "P$3") (pinfunction "VREF2_P$3") (pintype "bidirectional"))
      (node (ref "U19") (pin "P$7") (pinfunction "VREF1_P$7") (pintype "bidirectional"))
    )
    (net (code "114") (name "PANELREF") (class "Default")
      (node (ref "R13") (pin "1") (pinfunction "1_1") (pintype "passive"))
      (node (ref "R14") (pin "2") (pinfunction "2_2") (pintype "passive"))
      (node (ref "U2") (pin "P$6") (pinfunction "VIN3/REF_P$6") (pintype "bidirectional"))
    )
    (net (code "115") (name "SCL") (class "Default")
      (node (ref "R85") (pin "1") (pinfunction "1_1") (pintype "passive"))
      (node (ref "U1") (pin "P$22") (pinfunction "SCL_P$22") (pintype "bidirectional"))
      (node (ref "U2") (pin "P$1") (pinfunction "SCL_P$1") (pintype "bidirectional"))
      (node (ref "V5") (pin "P$1") (pinfunction "P$1_P$1") (pintype "bidirectional"))
    )
    (net (code "116") (name "SDA") (class "Default")
      (node (ref "R86") (pin "1") (pinfunction "1_1") (pintype "passive"))
      (node (ref "U1") (pin "P$23") (pinfunction "SDA_P$23") (pintype "bidirectional"))
      (node (ref "U2") (pin "P$2") (pinfunction "SDA_P$2") (pintype "bidirectional"))
      (node (ref "V6") (pin "P$1") (pinfunction "P$1_P$1") (pintype "bidirectional"))
    )
    (net (code "117") (name "SPF_ST") (class "Default")
      (node (ref "R83") (pin "1") (pinfunction "1_1") (pintype "passive"))
      (node (ref "U1") (pin "P$6") (pinfunction "P02_P$6") (pintype "bidirectional"))
      (node (ref "U3") (pin "P$4") (pinfunction "STAT_P$4") (pintype "bidirectional"))
    )
    (net (code "118") (name "SP_C") (class "Default")
      (node (ref "C3") (pin "1") (pinfunction "P$1_1") (pintype "passive"))
      (node (ref "M1") (pin "P$5") (pinfunction "D_P$5") (pintype "bidirectional"))
      (node (ref "M1") (pin "P$6") (pinfunction "D_P$6") (pintype "bidirectional"))
      (node (ref "M1") (pin "P$7") (pinfunction "D_P$7") (pintype "bidirectional"))
      (node (ref "M1") (pin "P$8") (pinfunction "D_P$8") (pintype "bidirectional"))
      (node (ref "R5") (pin "1") (pinfunction "1_1") (pintype "passive"))
      (node (ref "U3") (pin "P$1") (pinfunction "VIN_P$1") (pintype "bidirectional"))
      (node (ref "V13") (pin "P$1") (pinfunction "P$1_P$1") (pintype "bidirectional"))
      (node (ref "V14") (pin "P$1") (pinfunction "P$1_P$1") (pintype "bidirectional"))
      (node (ref "V15") (pin "P$1") (pinfunction "P$1_P$1") (pintype "bidirectional"))
      (node (ref "V16") (pin "P$1") (pinfunction "P$1_P$1") (pintype "bidirectional"))
      (node (ref "V17") (pin "P$1") (pinfunction "P$1_P$1") (pintype "bidirectional"))
      (node (ref "V18") (pin "P$1") (pinfunction "P$1_P$1") (pintype "bidirectional"))
    )
    (net (code "119") (name "SP_OUT") (class "Default")
      (node (ref "C17") (pin "1") (pinfunction "P$1_1") (pintype "passive"))
      (node (ref "C18") (pin "1") (pinfunction "P$1_1") (pintype "passive"))
      (node (ref "C25") (pin "2") (pinfunction "P$2_2") (pintype "passive"))
      (node (ref "C32") (pin "2") (pinfunction "P$2_2") (pintype "passive"))
      (node (ref "C4") (pin "1") (pinfunction "P$1_1") (pintype "passive"))
      (node (ref "C5") (pin "1") (pinfunction "P$1_1") (pintype "passive"))
      (node (ref "C6") (pin "1") (pinfunction "P$1_1") (pintype "passive"))
      (node (ref "D1") (pin "C") (pinfunction "C_C") (pintype "bidirectional"))
      (node (ref "M1") (pin "P$1") (pinfunction "S_P$1") (pintype "bidirectional"))
      (node (ref "M1") (pin "P$2") (pinfunction "S_P$2") (pintype "bidirectional"))
      (node (ref "M1") (pin "P$3") (pinfunction "S_P$3") (pintype "bidirectional"))
      (node (ref "R1") (pin "1") (pinfunction "1_1") (pintype "passive"))
      (node (ref "R10") (pin "2") (pinfunction "2_2") (pintype "passive"))
      (node (ref "R13") (pin "2") (pinfunction "2_2") (pintype "passive"))
      (node (ref "R15") (pin "1") (pinfunction "1_1") (pintype "passive"))
      (node (ref "R27") (pin "2") (pinfunction "2_2") (pintype "passive"))
      (node (ref "R45") (pin "2") (pinfunction "2_2") (pintype "passive"))
      (node (ref "R5") (pin "2") (pinfunction "2_2") (pintype "passive"))
      (node (ref "R63") (pin "2") (pinfunction "2_2") (pintype "passive"))
      (node (ref "U10") (pin "P$5") (pinfunction "~{SHDN}_P$5") (pintype "bidirectional"))
      (node (ref "U10") (pin "P$8") (pinfunction "IN_P$8") (pintype "bidirectional"))
      (node (ref "U11") (pin "P$5") (pinfunction "~{SHDN}_P$5") (pintype "bidirectional"))
      (node (ref "U11") (pin "P$8") (pinfunction "IN_P$8") (pintype "bidirectional"))
      (node (ref "U14") (pin "P$3") (pinfunction "IN_P$3") (pintype "bidirectional"))
      (node (ref "U16") (pin "P$3") (pinfunction "IN_P$3") (pintype "bidirectional"))
      (node (ref "U3") (pin "P$6") (pinfunction "SNS_P$6") (pintype "bidirectional"))
      (node (ref "U4") (pin "P$3") (pinfunction "IN_P$3") (pintype "bidirectional"))
      (node (ref "U5") (pin "P$3") (pinfunction "IN_P$3") (pintype "bidirectional"))
    )
    (net (code "120") (name "UMB_CHG") (class "Default")
      (node (ref "D1") (pin "A") (pinfunction "A_A") (pintype "bidirectional"))
      (node (ref "V19") (pin "P$1") (pinfunction "P$1_P$1") (pintype "bidirectional"))
    )
    (net (code "121") (name "~{BATT_INT}") (class "Default")
      (node (ref "R84") (pin "1") (pinfunction "1_1") (pintype "passive"))
      (node (ref "U1") (pin "P$1") (pinfunction "~{INT}_P$1") (pintype "bidirectional"))
    )
  )
)
